# otterley_B_v1_2.net
KiCad netlist of a schematic drawn in EAGLE
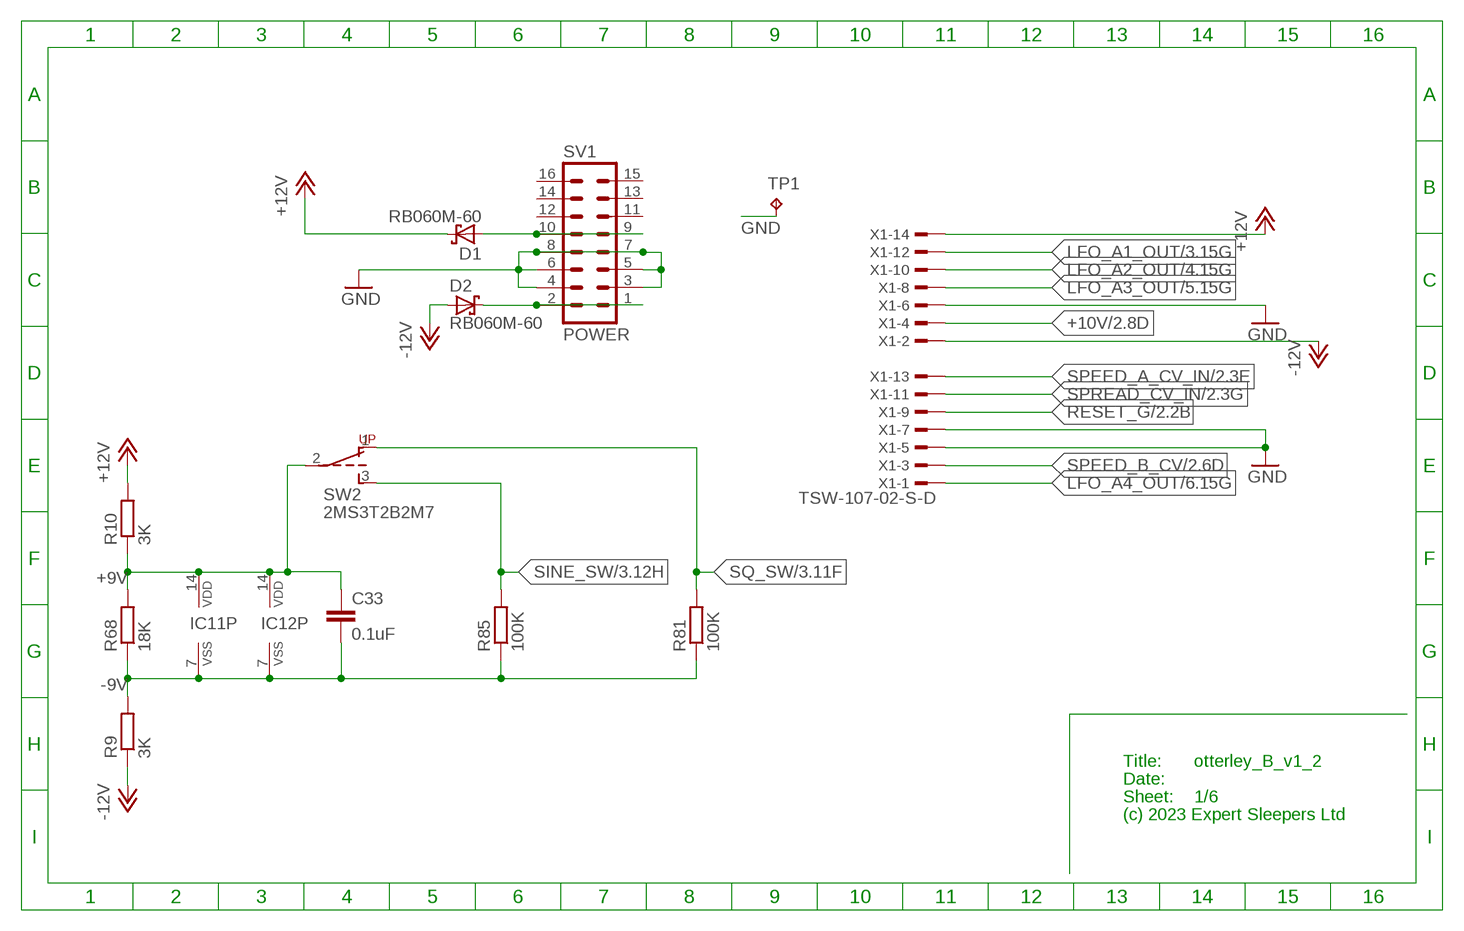
[diagram p0: schematic, sheet 1]
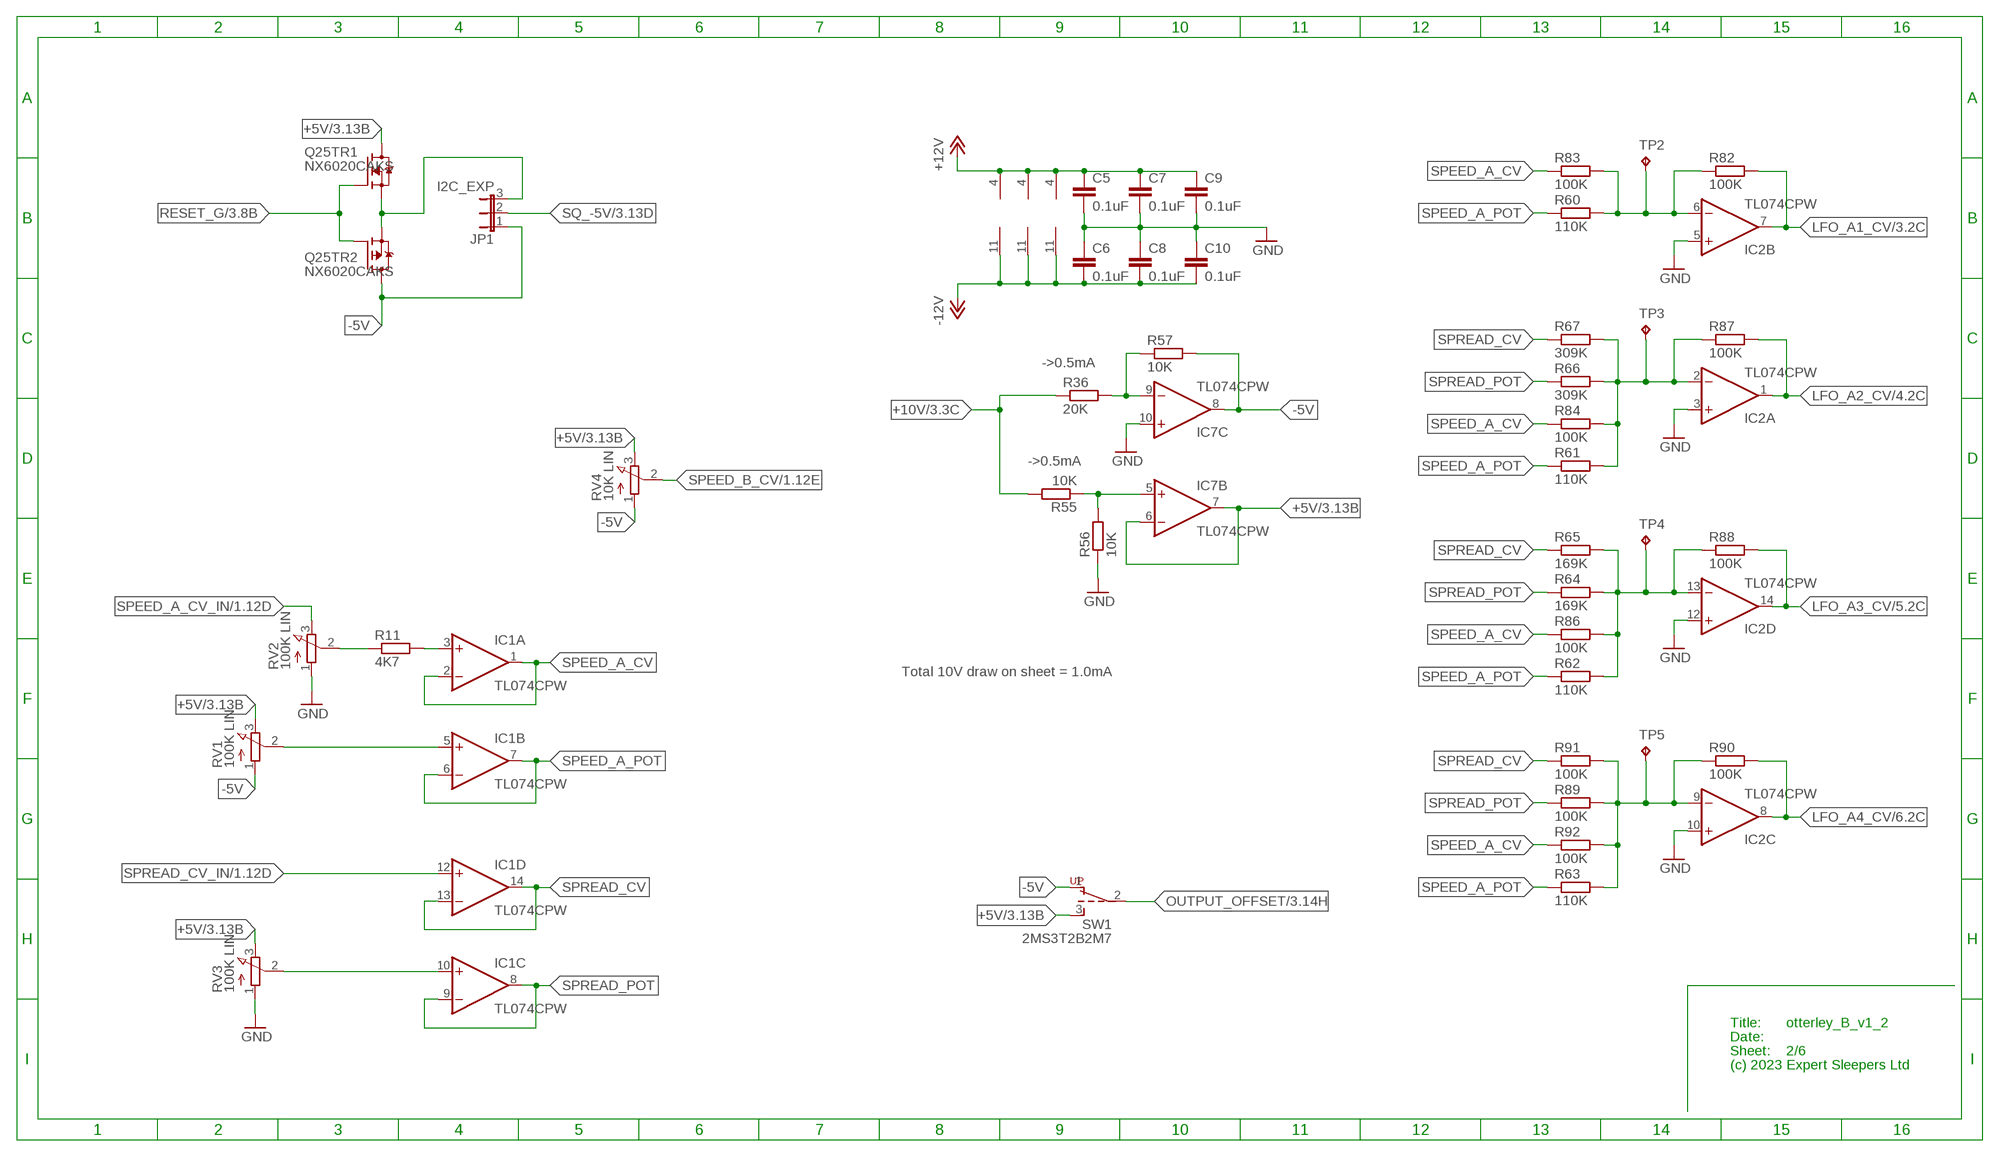
[diagram p1: schematic, sheet 2]
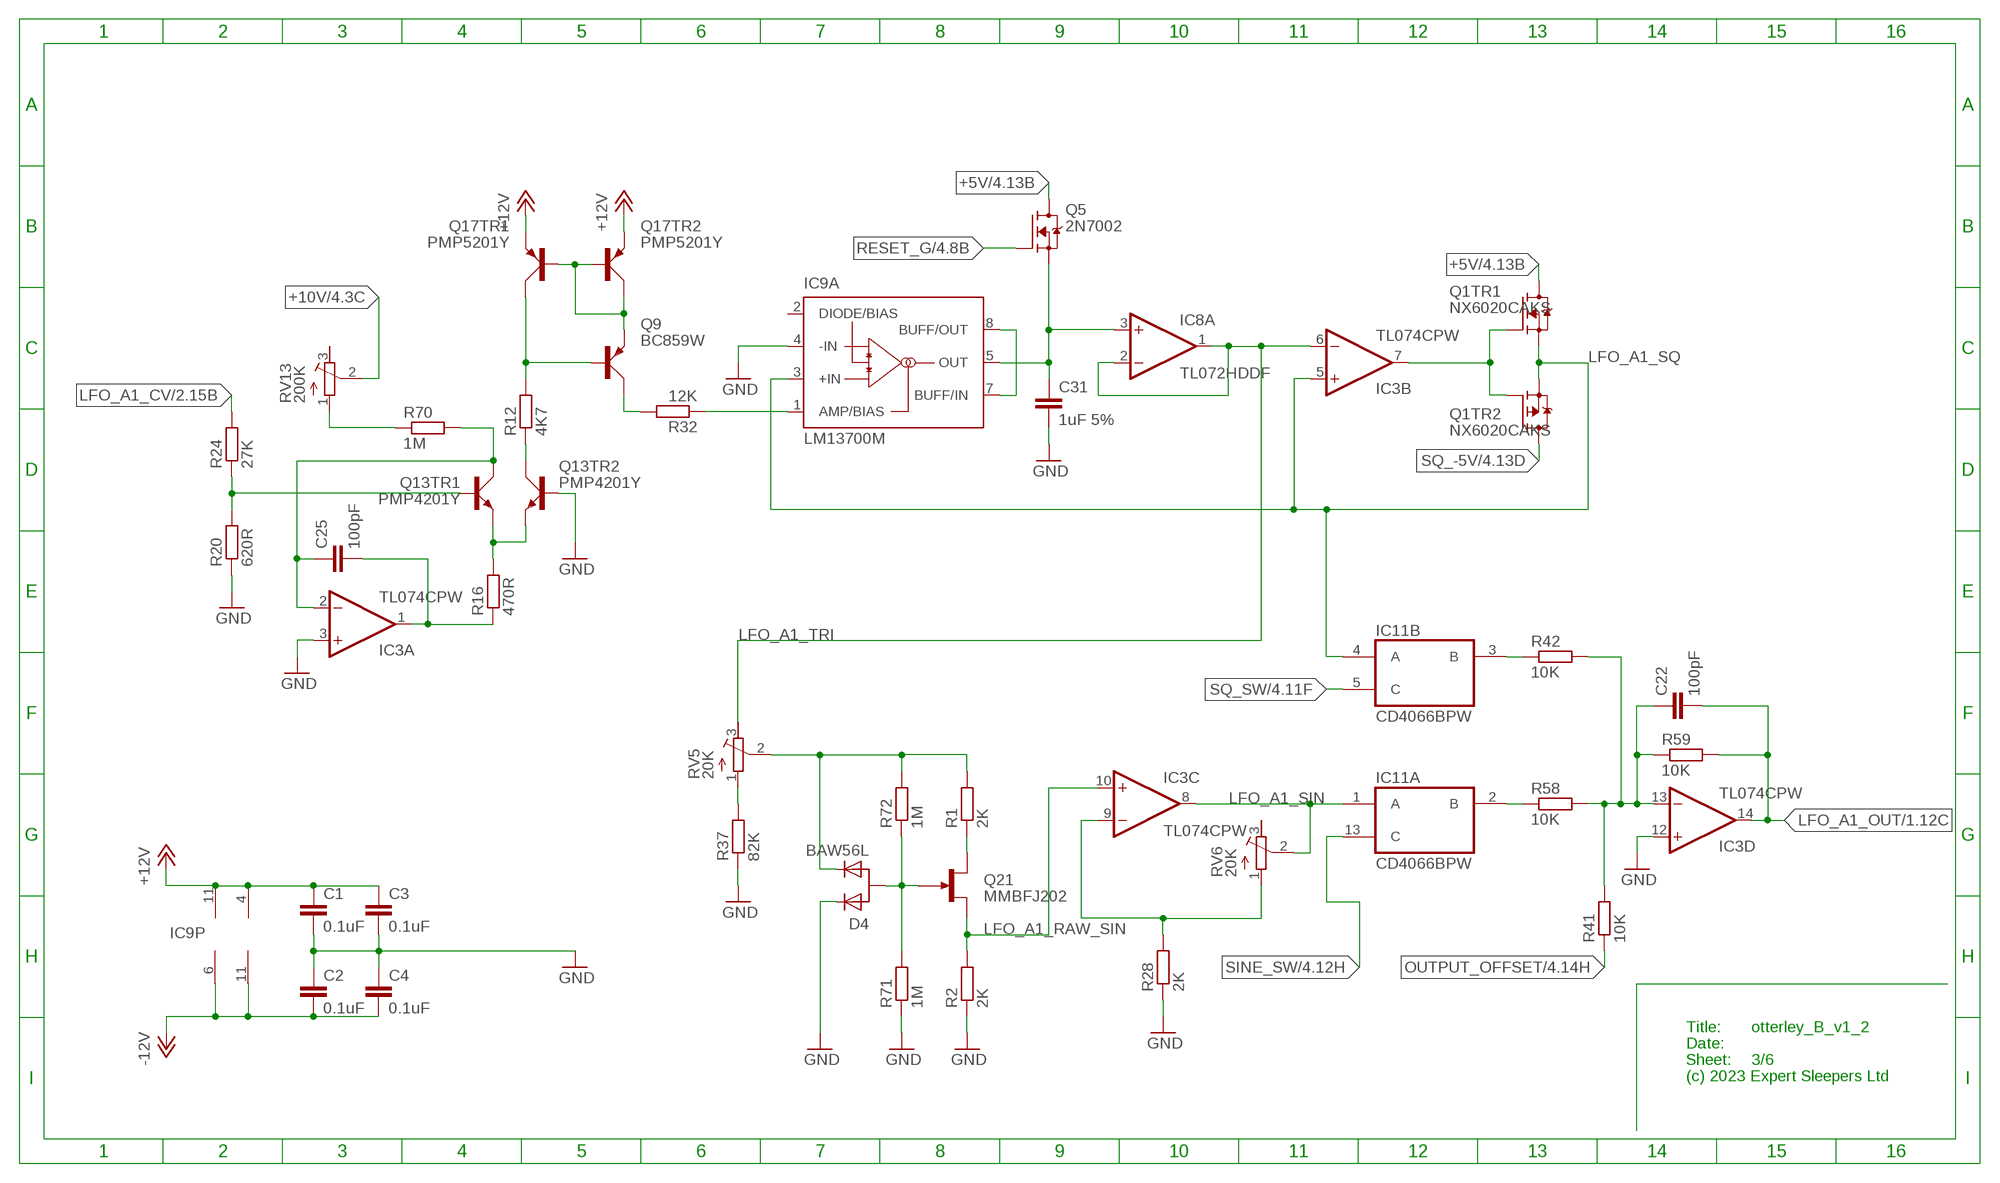
[diagram p2: schematic, sheet 3]
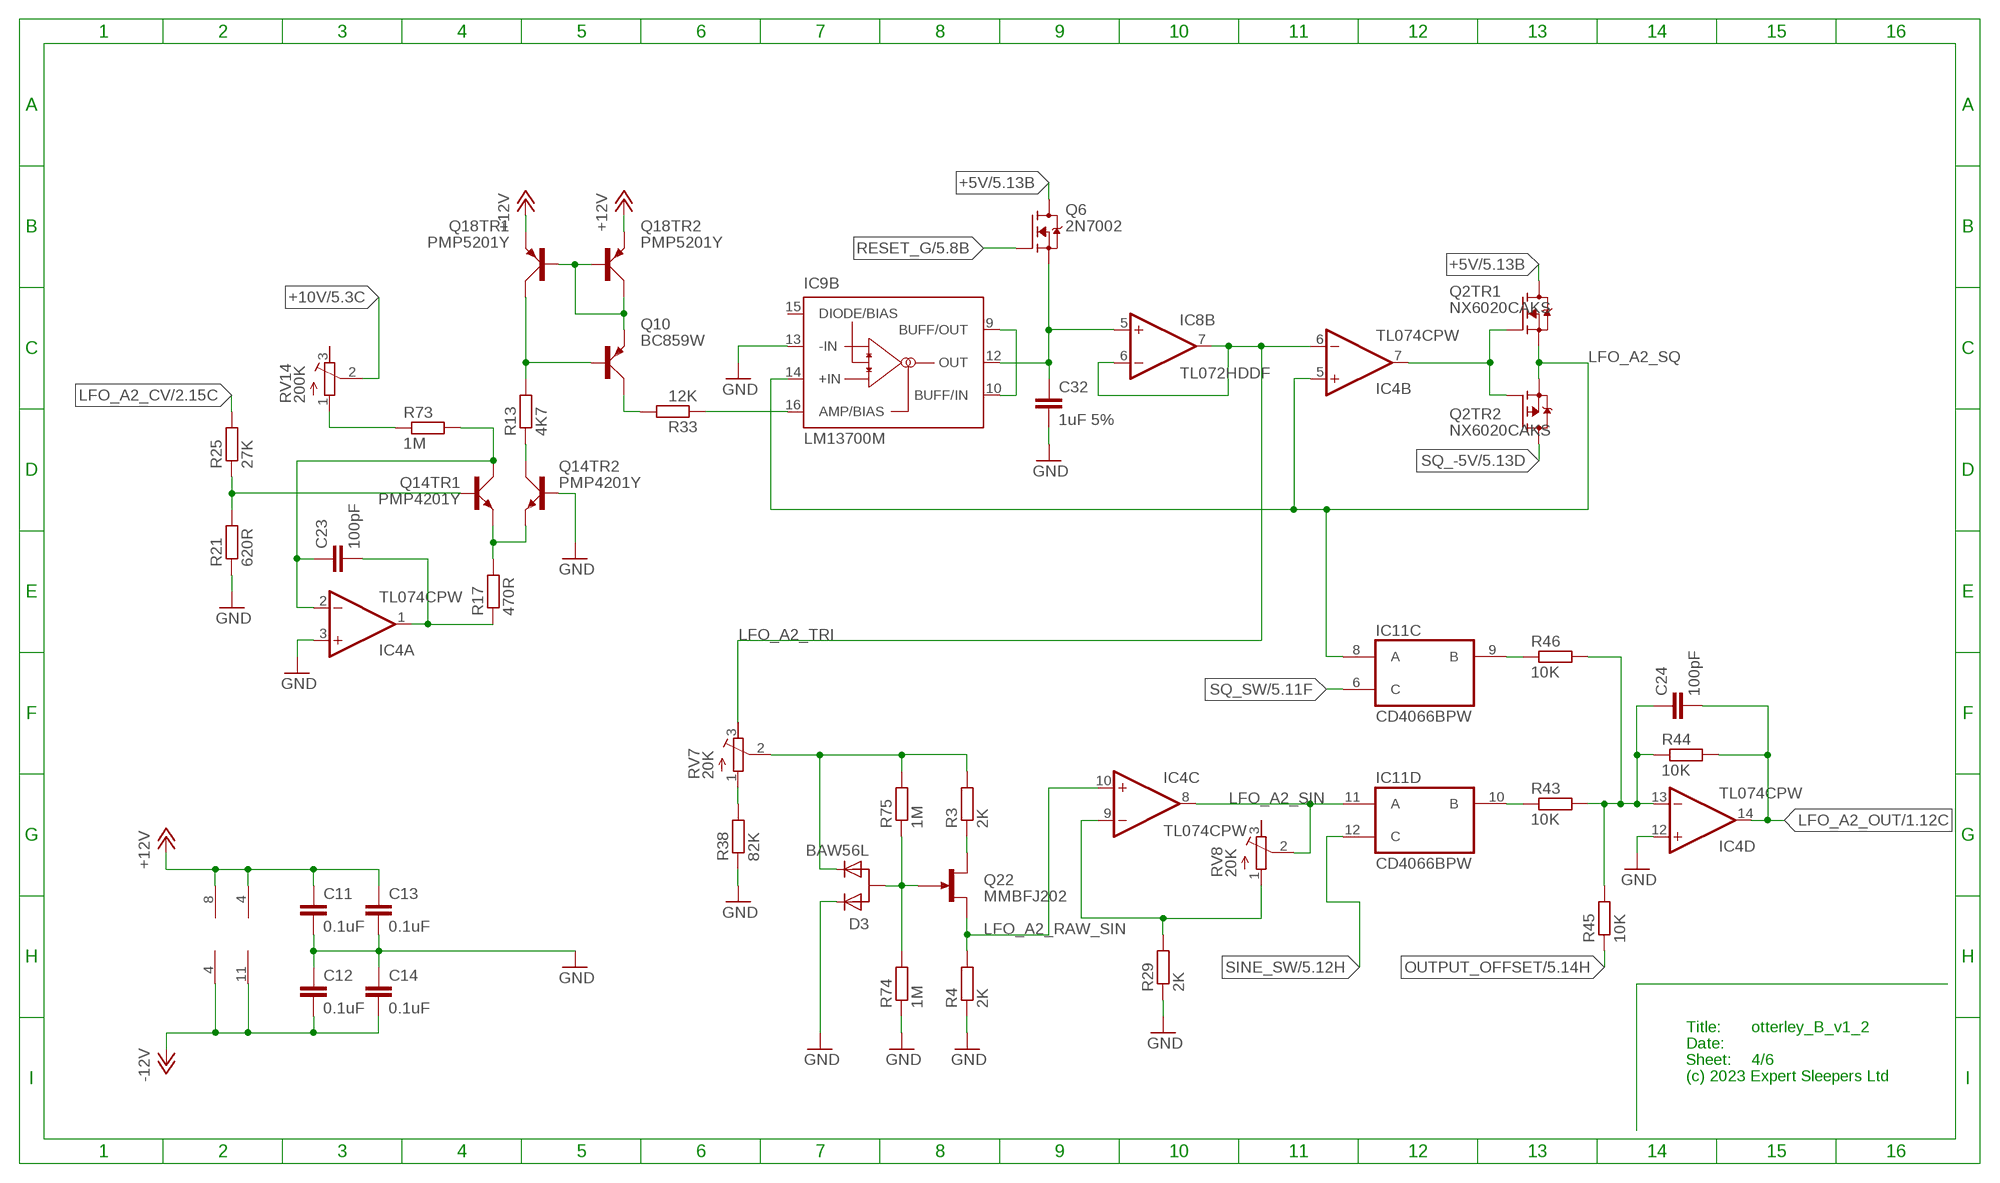
[diagram p3: schematic, sheet 4]
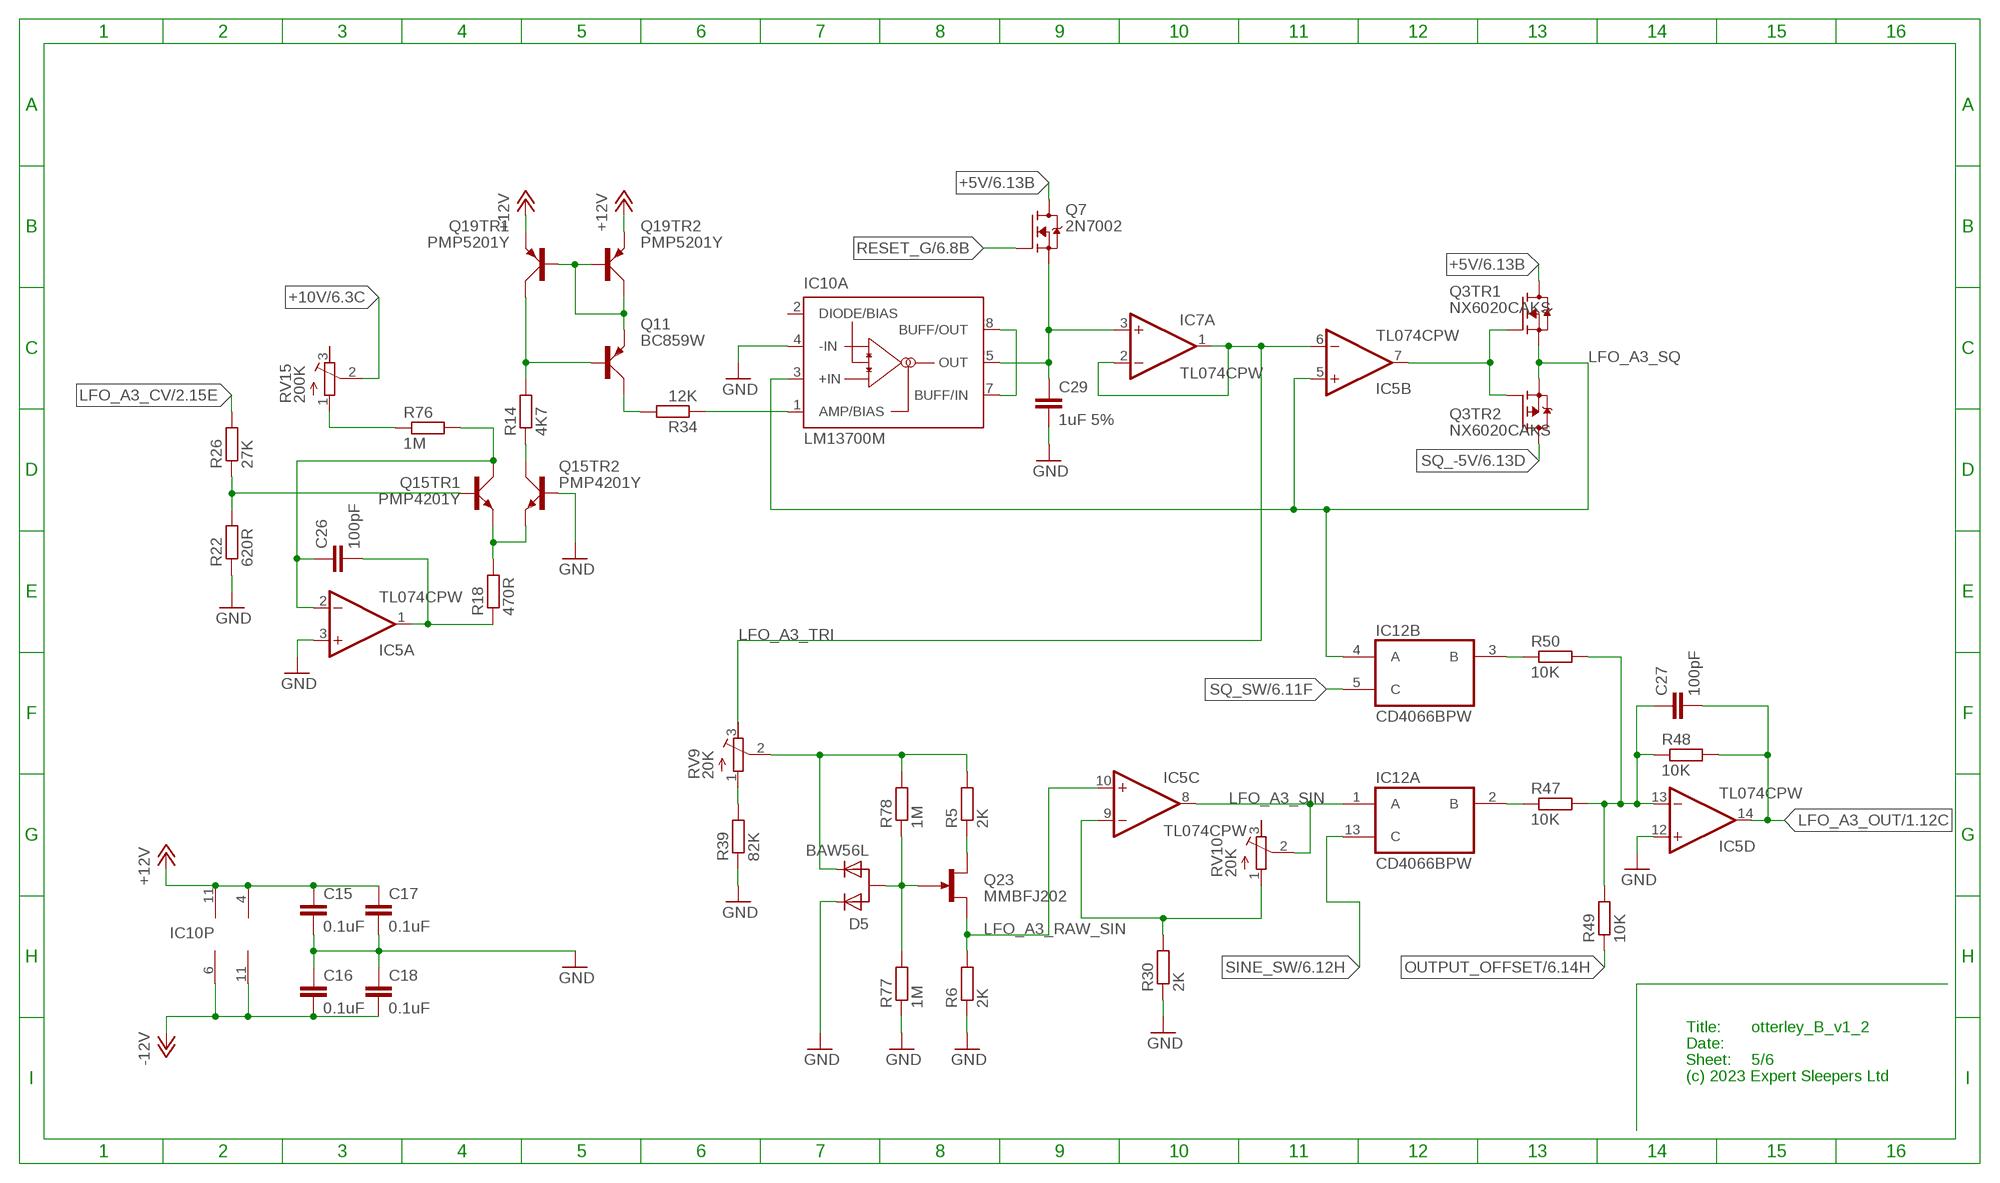
[diagram p4: schematic, sheet 5]
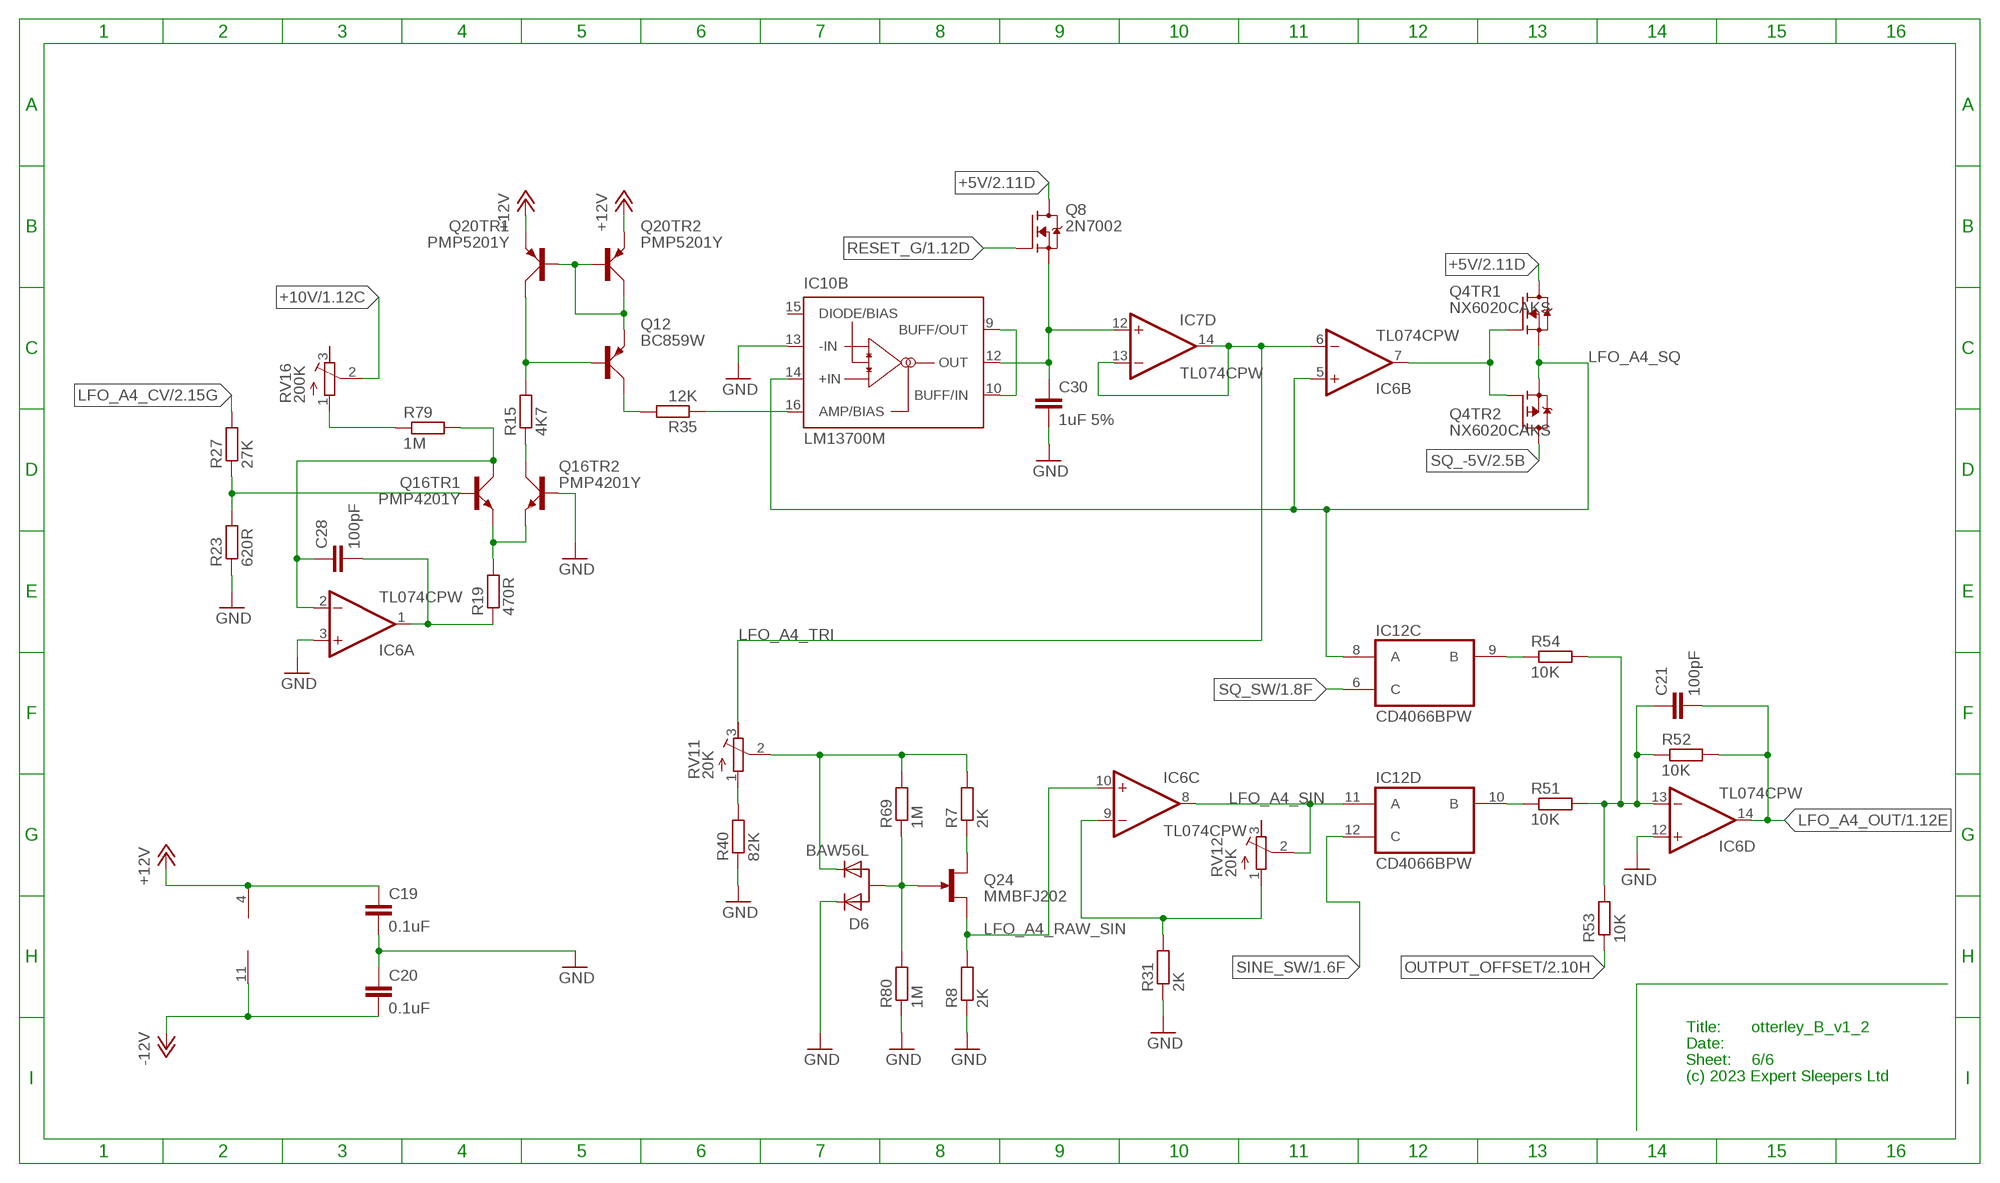
[diagram p5: schematic, sheet 6]

(export (version "E")
  (design (tool "Eeschema 10.0.6"))
  (components
    (comp (ref "C15")
      (value "0.1uF")
      (footprint "eagle-import:C0402")
      (libsource (lib "eagle-import") (part "C-EUC0402"))
    )
    (comp (ref "C16")
      (value "0.1uF")
      (footprint "eagle-import:C0402")
      (libsource (lib "eagle-import") (part "C-EUC0402"))
    )
    (comp (ref "C17")
      (value "0.1uF")
      (footprint "eagle-import:C0402")
      (libsource (lib "eagle-import") (part "C-EUC0402"))
    )
    (comp (ref "C18")
      (value "0.1uF")
      (footprint "eagle-import:C0402")
      (libsource (lib "eagle-import") (part "C-EUC0402"))
    )
    (comp (ref "C26")
      (value "100pF")
      (footprint "eagle-import:C0603")
      (libsource (lib "eagle-import") (part "C-EUC0603"))
    )
    (comp (ref "C27")
      (value "100pF")
      (footprint "eagle-import:C0603")
      (libsource (lib "eagle-import") (part "C-EUC0603"))
    )
    (comp (ref "C29")
      (value "1uF 5%")
      (footprint "eagle-import:C0805")
      (libsource (lib "eagle-import") (part "C-EUC0805"))
    )
    (comp (ref "D5")
      (value "BAW56L")
      (footprint "eagle-import:SOT-23")
      (libsource (lib "eagle-import") (part "BAW56L"))
    )
    (comp (ref "IC5")
      (value "TL074CPW")
      (footprint "eagle-import:PW_R-PDSO-G14")
      (libsource (lib "eagle-import") (part "TL074PW"))
    )
    (comp (ref "IC7")
      (value "TL074CPW")
      (footprint "eagle-import:PW_R-PDSO-G14")
      (libsource (lib "eagle-import") (part "TL074PW"))
    )
    (comp (ref "IC10")
      (value "LM13700M")
      (footprint "eagle-import:SO16")
      (libsource (lib "eagle-import") (part "LM13700M"))
    )
    (comp (ref "IC12")
      (value "CD4066BPW")
      (footprint "eagle-import:PW_R-PDSO-G14")
      (libsource (lib "eagle-import") (part "CD4066BPW"))
    )
    (comp (ref "Q3")
      (value "NX6020CAKS")
      (footprint "eagle-import:SOT363")
      (libsource (lib "eagle-import") (part "NX6020CAKS"))
    )
    (comp (ref "Q7")
      (value "2N7002")
      (footprint "eagle-import:SOT23")
      (libsource (lib "eagle-import") (part "2N7002"))
    )
    (comp (ref "Q11")
      (value "BC859W")
      (footprint "eagle-import:SOT323")
      (libsource (lib "eagle-import") (part "BC859W"))
    )
    (comp (ref "Q15")
      (value "PMP4201Y")
      (footprint "eagle-import:SOT65P210X110-6N")
      (fields
        (field (name "ARROW_PART_NUMBER") "PMP4201Y,135")
        (field (name "MOUSER_PART_NUMBER") "771-PMP4201Y135")
      )
      (libsource (lib "eagle-import") (part "PMP4201Y"))
    )
    (comp (ref "Q19")
      (value "PMP5201Y")
      (footprint "eagle-import:SOT65P210X110-6N")
      (fields
        (field (name "ARROW_PART_NUMBER") "PMP5201Y,135")
        (field (name "MOUSER_PART_NUMBER") "771-PMP5201Y135")
      )
      (libsource (lib "eagle-import") (part "PMP5201Y"))
    )
    (comp (ref "Q23")
      (value "MMBFJ202")
      (footprint "eagle-import:SOT23")
      (libsource (lib "eagle-import") (part "MMBFJ3"))
    )
    (comp (ref "R5")
      (value "2K")
      (footprint "eagle-import:R0603")
      (libsource (lib "eagle-import") (part "R-EU_R0603"))
    )
    (comp (ref "R6")
      (value "2K")
      (footprint "eagle-import:R0603")
      (libsource (lib "eagle-import") (part "R-EU_R0603"))
    )
    (comp (ref "R14")
      (value "4K7")
      (footprint "eagle-import:R0603")
      (libsource (lib "eagle-import") (part "R-EU_R0603"))
    )
    (comp (ref "R18")
      (value "470R")
      (footprint "eagle-import:R0603")
      (libsource (lib "eagle-import") (part "R-EU_R0603"))
    )
    (comp (ref "R22")
      (value "620R")
      (footprint "eagle-import:R0603")
      (libsource (lib "eagle-import") (part "R-EU_R0603"))
    )
    (comp (ref "R26")
      (value "27K")
      (footprint "eagle-import:R0603")
      (libsource (lib "eagle-import") (part "R-EU_R0603"))
    )
    (comp (ref "R30")
      (value "2K")
      (footprint "eagle-import:R0603")
      (libsource (lib "eagle-import") (part "R-EU_R0603"))
    )
    (comp (ref "R34")
      (value "12K")
      (footprint "eagle-import:R0603")
      (libsource (lib "eagle-import") (part "R-EU_R0603"))
    )
    (comp (ref "R39")
      (value "82K")
      (footprint "eagle-import:R0603")
      (libsource (lib "eagle-import") (part "R-EU_R0603"))
    )
    (comp (ref "R47")
      (value "10K")
      (footprint "eagle-import:R0603")
      (libsource (lib "eagle-import") (part "R-EU_R0603"))
    )
    (comp (ref "R48")
      (value "10K")
      (footprint "eagle-import:R0603")
      (libsource (lib "eagle-import") (part "R-EU_R0603"))
    )
    (comp (ref "R49")
      (value "10K")
      (footprint "eagle-import:R0603")
      (libsource (lib "eagle-import") (part "R-EU_R0603"))
    )
    (comp (ref "R50")
      (value "10K")
      (footprint "eagle-import:R0603")
      (libsource (lib "eagle-import") (part "R-EU_R0603"))
    )
    (comp (ref "R76")
      (value "1M")
      (footprint "eagle-import:R0603")
      (libsource (lib "eagle-import") (part "R-EU_R0603"))
    )
    (comp (ref "R77")
      (value "1M")
      (footprint "eagle-import:R0603")
      (libsource (lib "eagle-import") (part "R-EU_R0603"))
    )
    (comp (ref "R78")
      (value "1M")
      (footprint "eagle-import:R0603")
      (libsource (lib "eagle-import") (part "R-EU_R0603"))
    )
    (comp (ref "RV9")
      (value "20K")
      (footprint "eagle-import:TC33X")
      (libsource (lib "eagle-import") (part "TC33X"))
    )
    (comp (ref "RV10")
      (value "20K")
      (footprint "eagle-import:TC33X")
      (libsource (lib "eagle-import") (part "TC33X"))
    )
    (comp (ref "RV15")
      (value "200K")
      (footprint "eagle-import:TC33X")
      (libsource (lib "eagle-import") (part "TC33X"))
    )
    (comp (ref "C1")
      (value "0.1uF")
      (footprint "eagle-import:C0402")
      (libsource (lib "eagle-import") (part "C-EUC0402"))
    )
    (comp (ref "C2")
      (value "0.1uF")
      (footprint "eagle-import:C0402")
      (libsource (lib "eagle-import") (part "C-EUC0402"))
    )
    (comp (ref "C3")
      (value "0.1uF")
      (footprint "eagle-import:C0402")
      (libsource (lib "eagle-import") (part "C-EUC0402"))
    )
    (comp (ref "C4")
      (value "0.1uF")
      (footprint "eagle-import:C0402")
      (libsource (lib "eagle-import") (part "C-EUC0402"))
    )
    (comp (ref "C22")
      (value "100pF")
      (footprint "eagle-import:C0603")
      (libsource (lib "eagle-import") (part "C-EUC0603"))
    )
    (comp (ref "C25")
      (value "100pF")
      (footprint "eagle-import:C0603")
      (libsource (lib "eagle-import") (part "C-EUC0603"))
    )
    (comp (ref "C31")
      (value "1uF 5%")
      (footprint "eagle-import:C0805")
      (libsource (lib "eagle-import") (part "C-EUC0805"))
    )
    (comp (ref "D4")
      (value "BAW56L")
      (footprint "eagle-import:SOT-23")
      (libsource (lib "eagle-import") (part "BAW56L"))
    )
    (comp (ref "IC3")
      (value "TL074CPW")
      (footprint "eagle-import:PW_R-PDSO-G14")
      (libsource (lib "eagle-import") (part "TL074PW"))
    )
    (comp (ref "IC8")
      (value "TL072HDDF")
      (footprint "eagle-import:DDF0008A")
      (libsource (lib "eagle-import") (part "TL072DDFH"))
    )
    (comp (ref "IC9")
      (value "LM13700M")
      (footprint "eagle-import:SO16")
      (libsource (lib "eagle-import") (part "LM13700M"))
    )
    (comp (ref "IC11")
      (value "CD4066BPW")
      (footprint "eagle-import:PW_R-PDSO-G14")
      (libsource (lib "eagle-import") (part "CD4066BPW"))
    )
    (comp (ref "Q1")
      (value "NX6020CAKS")
      (footprint "eagle-import:SOT363")
      (libsource (lib "eagle-import") (part "NX6020CAKS"))
    )
    (comp (ref "Q5")
      (value "2N7002")
      (footprint "eagle-import:SOT23")
      (libsource (lib "eagle-import") (part "2N7002"))
    )
    (comp (ref "Q9")
      (value "BC859W")
      (footprint "eagle-import:SOT323")
      (libsource (lib "eagle-import") (part "BC859W"))
    )
    (comp (ref "Q13")
      (value "PMP4201Y")
      (footprint "eagle-import:SOT65P210X110-6N")
      (fields
        (field (name "ARROW_PART_NUMBER") "PMP4201Y,135")
        (field (name "MOUSER_PART_NUMBER") "771-PMP4201Y135")
      )
      (libsource (lib "eagle-import") (part "PMP4201Y"))
    )
    (comp (ref "Q17")
      (value "PMP5201Y")
      (footprint "eagle-import:SOT65P210X110-6N")
      (fields
        (field (name "ARROW_PART_NUMBER") "PMP5201Y,135")
        (field (name "MOUSER_PART_NUMBER") "771-PMP5201Y135")
      )
      (libsource (lib "eagle-import") (part "PMP5201Y"))
    )
    (comp (ref "Q21")
      (value "MMBFJ202")
      (footprint "eagle-import:SOT23")
      (libsource (lib "eagle-import") (part "MMBFJ3"))
    )
    (comp (ref "R1")
      (value "2K")
      (footprint "eagle-import:R0603")
      (libsource (lib "eagle-import") (part "R-EU_R0603"))
    )
    (comp (ref "R2")
      (value "2K")
      (footprint "eagle-import:R0603")
      (libsource (lib "eagle-import") (part "R-EU_R0603"))
    )
    (comp (ref "R12")
      (value "4K7")
      (footprint "eagle-import:R0603")
      (libsource (lib "eagle-import") (part "R-EU_R0603"))
    )
    (comp (ref "R16")
      (value "470R")
      (footprint "eagle-import:R0603")
      (libsource (lib "eagle-import") (part "R-EU_R0603"))
    )
    (comp (ref "R20")
      (value "620R")
      (footprint "eagle-import:R0603")
      (libsource (lib "eagle-import") (part "R-EU_R0603"))
    )
    (comp (ref "R24")
      (value "27K")
      (footprint "eagle-import:R0603")
      (libsource (lib "eagle-import") (part "R-EU_R0603"))
    )
    (comp (ref "R28")
      (value "2K")
      (footprint "eagle-import:R0603")
      (libsource (lib "eagle-import") (part "R-EU_R0603"))
    )
    (comp (ref "R32")
      (value "12K")
      (footprint "eagle-import:R0603")
      (libsource (lib "eagle-import") (part "R-EU_R0603"))
    )
    (comp (ref "R37")
      (value "82K")
      (footprint "eagle-import:R0603")
      (libsource (lib "eagle-import") (part "R-EU_R0603"))
    )
    (comp (ref "R41")
      (value "10K")
      (footprint "eagle-import:R0603")
      (libsource (lib "eagle-import") (part "R-EU_R0603"))
    )
    (comp (ref "R42")
      (value "10K")
      (footprint "eagle-import:R0603")
      (libsource (lib "eagle-import") (part "R-EU_R0603"))
    )
    (comp (ref "R58")
      (value "10K")
      (footprint "eagle-import:R0603")
      (libsource (lib "eagle-import") (part "R-EU_R0603"))
    )
    (comp (ref "R59")
      (value "10K")
      (footprint "eagle-import:R0603")
      (libsource (lib "eagle-import") (part "R-EU_R0603"))
    )
    (comp (ref "R70")
      (value "1M")
      (footprint "eagle-import:R0603")
      (libsource (lib "eagle-import") (part "R-EU_R0603"))
    )
    (comp (ref "R71")
      (value "1M")
      (footprint "eagle-import:R0603")
      (libsource (lib "eagle-import") (part "R-EU_R0603"))
    )
    (comp (ref "R72")
      (value "1M")
      (footprint "eagle-import:R0603")
      (libsource (lib "eagle-import") (part "R-EU_R0603"))
    )
    (comp (ref "RV5")
      (value "20K")
      (footprint "eagle-import:TC33X")
      (libsource (lib "eagle-import") (part "TC33X"))
    )
    (comp (ref "RV6")
      (value "20K")
      (footprint "eagle-import:TC33X")
      (libsource (lib "eagle-import") (part "TC33X"))
    )
    (comp (ref "RV13")
      (value "200K")
      (footprint "eagle-import:TC33X")
      (libsource (lib "eagle-import") (part "TC33X"))
    )
    (comp (ref "C11")
      (value "0.1uF")
      (footprint "eagle-import:C0402")
      (libsource (lib "eagle-import") (part "C-EUC0402"))
    )
    (comp (ref "C12")
      (value "0.1uF")
      (footprint "eagle-import:C0402")
      (libsource (lib "eagle-import") (part "C-EUC0402"))
    )
    (comp (ref "C13")
      (value "0.1uF")
      (footprint "eagle-import:C0402")
      (libsource (lib "eagle-import") (part "C-EUC0402"))
    )
    (comp (ref "C14")
      (value "0.1uF")
      (footprint "eagle-import:C0402")
      (libsource (lib "eagle-import") (part "C-EUC0402"))
    )
    (comp (ref "C23")
      (value "100pF")
      (footprint "eagle-import:C0603")
      (libsource (lib "eagle-import") (part "C-EUC0603"))
    )
    (comp (ref "C24")
      (value "100pF")
      (footprint "eagle-import:C0603")
      (libsource (lib "eagle-import") (part "C-EUC0603"))
    )
    (comp (ref "C32")
      (value "1uF 5%")
      (footprint "eagle-import:C0805")
      (libsource (lib "eagle-import") (part "C-EUC0805"))
    )
    (comp (ref "D3")
      (value "BAW56L")
      (footprint "eagle-import:SOT-23")
      (libsource (lib "eagle-import") (part "BAW56L"))
    )
    (comp (ref "IC4")
      (value "TL074CPW")
      (footprint "eagle-import:PW_R-PDSO-G14")
      (libsource (lib "eagle-import") (part "TL074PW"))
    )
    (comp (ref "Q2")
      (value "NX6020CAKS")
      (footprint "eagle-import:SOT363")
      (libsource (lib "eagle-import") (part "NX6020CAKS"))
    )
    (comp (ref "Q6")
      (value "2N7002")
      (footprint "eagle-import:SOT23")
      (libsource (lib "eagle-import") (part "2N7002"))
    )
    (comp (ref "Q10")
      (value "BC859W")
      (footprint "eagle-import:SOT323")
      (libsource (lib "eagle-import") (part "BC859W"))
    )
    (comp (ref "Q14")
      (value "PMP4201Y")
      (footprint "eagle-import:SOT65P210X110-6N")
      (fields
        (field (name "ARROW_PART_NUMBER") "PMP4201Y,135")
        (field (name "MOUSER_PART_NUMBER") "771-PMP4201Y135")
      )
      (libsource (lib "eagle-import") (part "PMP4201Y"))
    )
    (comp (ref "Q18")
      (value "PMP5201Y")
      (footprint "eagle-import:SOT65P210X110-6N")
      (fields
        (field (name "ARROW_PART_NUMBER") "PMP5201Y,135")
        (field (name "MOUSER_PART_NUMBER") "771-PMP5201Y135")
      )
      (libsource (lib "eagle-import") (part "PMP5201Y"))
    )
    (comp (ref "Q22")
      (value "MMBFJ202")
      (footprint "eagle-import:SOT23")
      (libsource (lib "eagle-import") (part "MMBFJ3"))
    )
    (comp (ref "R3")
      (value "2K")
      (footprint "eagle-import:R0603")
      (libsource (lib "eagle-import") (part "R-EU_R0603"))
    )
    (comp (ref "R4")
      (value "2K")
      (footprint "eagle-import:R0603")
      (libsource (lib "eagle-import") (part "R-EU_R0603"))
    )
    (comp (ref "R13")
      (value "4K7")
      (footprint "eagle-import:R0603")
      (libsource (lib "eagle-import") (part "R-EU_R0603"))
    )
    (comp (ref "R17")
      (value "470R")
      (footprint "eagle-import:R0603")
      (libsource (lib "eagle-import") (part "R-EU_R0603"))
    )
    (comp (ref "R21")
      (value "620R")
      (footprint "eagle-import:R0603")
      (libsource (lib "eagle-import") (part "R-EU_R0603"))
    )
    (comp (ref "R25")
      (value "27K")
      (footprint "eagle-import:R0603")
      (libsource (lib "eagle-import") (part "R-EU_R0603"))
    )
    (comp (ref "R29")
      (value "2K")
      (footprint "eagle-import:R0603")
      (libsource (lib "eagle-import") (part "R-EU_R0603"))
    )
    (comp (ref "R33")
      (value "12K")
      (footprint "eagle-import:R0603")
      (libsource (lib "eagle-import") (part "R-EU_R0603"))
    )
    (comp (ref "R38")
      (value "82K")
      (footprint "eagle-import:R0603")
      (libsource (lib "eagle-import") (part "R-EU_R0603"))
    )
    (comp (ref "R43")
      (value "10K")
      (footprint "eagle-import:R0603")
      (libsource (lib "eagle-import") (part "R-EU_R0603"))
    )
    (comp (ref "R44")
      (value "10K")
      (footprint "eagle-import:R0603")
      (libsource (lib "eagle-import") (part "R-EU_R0603"))
    )
    (comp (ref "R45")
      (value "10K")
      (footprint "eagle-import:R0603")
      (libsource (lib "eagle-import") (part "R-EU_R0603"))
    )
    (comp (ref "R46")
      (value "10K")
      (footprint "eagle-import:R0603")
      (libsource (lib "eagle-import") (part "R-EU_R0603"))
    )
    (comp (ref "R73")
      (value "1M")
      (footprint "eagle-import:R0603")
      (libsource (lib "eagle-import") (part "R-EU_R0603"))
    )
    (comp (ref "R74")
      (value "1M")
      (footprint "eagle-import:R0603")
      (libsource (lib "eagle-import") (part "R-EU_R0603"))
    )
    (comp (ref "R75")
      (value "1M")
      (footprint "eagle-import:R0603")
      (libsource (lib "eagle-import") (part "R-EU_R0603"))
    )
    (comp (ref "RV7")
      (value "20K")
      (footprint "eagle-import:TC33X")
      (libsource (lib "eagle-import") (part "TC33X"))
    )
    (comp (ref "RV8")
      (value "20K")
      (footprint "eagle-import:TC33X")
      (libsource (lib "eagle-import") (part "TC33X"))
    )
    (comp (ref "RV14")
      (value "200K")
      (footprint "eagle-import:TC33X")
      (libsource (lib "eagle-import") (part "TC33X"))
    )
    (comp (ref "C19")
      (value "0.1uF")
      (footprint "eagle-import:C0402")
      (libsource (lib "eagle-import") (part "C-EUC0402"))
    )
    (comp (ref "C20")
      (value "0.1uF")
      (footprint "eagle-import:C0402")
      (libsource (lib "eagle-import") (part "C-EUC0402"))
    )
    (comp (ref "C21")
      (value "100pF")
      (footprint "eagle-import:C0603")
      (libsource (lib "eagle-import") (part "C-EUC0603"))
    )
    (comp (ref "C28")
      (value "100pF")
      (footprint "eagle-import:C0603")
      (libsource (lib "eagle-import") (part "C-EUC0603"))
    )
    (comp (ref "C30")
      (value "1uF 5%")
      (footprint "eagle-import:C0805")
      (libsource (lib "eagle-import") (part "C-EUC0805"))
    )
    (comp (ref "D6")
      (value "BAW56L")
      (footprint "eagle-import:SOT-23")
      (libsource (lib "eagle-import") (part "BAW56L"))
    )
    (comp (ref "IC6")
      (value "TL074CPW")
      (footprint "eagle-import:PW_R-PDSO-G14")
      (libsource (lib "eagle-import") (part "TL074PW"))
    )
    (comp (ref "Q4")
      (value "NX6020CAKS")
      (footprint "eagle-import:SOT363")
      (libsource (lib "eagle-import") (part "NX6020CAKS"))
    )
    (comp (ref "Q8")
      (value "2N7002")
      (footprint "eagle-import:SOT23")
      (libsource (lib "eagle-import") (part "2N7002"))
    )
    (comp (ref "Q12")
      (value "BC859W")
      (footprint "eagle-import:SOT323")
      (libsource (lib "eagle-import") (part "BC859W"))
    )
    (comp (ref "Q16")
      (value "PMP4201Y")
      (footprint "eagle-import:SOT65P210X110-6N")
      (fields
        (field (name "ARROW_PART_NUMBER") "PMP4201Y,135")
        (field (name "MOUSER_PART_NUMBER") "771-PMP4201Y135")
      )
      (libsource (lib "eagle-import") (part "PMP4201Y"))
    )
    (comp (ref "Q20")
      (value "PMP5201Y")
      (footprint "eagle-import:SOT65P210X110-6N")
      (fields
        (field (name "ARROW_PART_NUMBER") "PMP5201Y,135")
        (field (name "MOUSER_PART_NUMBER") "771-PMP5201Y135")
      )
      (libsource (lib "eagle-import") (part "PMP5201Y"))
    )
    (comp (ref "Q24")
      (value "MMBFJ202")
      (footprint "eagle-import:SOT23")
      (libsource (lib "eagle-import") (part "MMBFJ3"))
    )
    (comp (ref "R7")
      (value "2K")
      (footprint "eagle-import:R0603")
      (libsource (lib "eagle-import") (part "R-EU_R0603"))
    )
    (comp (ref "R8")
      (value "2K")
      (footprint "eagle-import:R0603")
      (libsource (lib "eagle-import") (part "R-EU_R0603"))
    )
    (comp (ref "R15")
      (value "4K7")
      (footprint "eagle-import:R0603")
      (libsource (lib "eagle-import") (part "R-EU_R0603"))
    )
    (comp (ref "R19")
      (value "470R")
      (footprint "eagle-import:R0603")
      (libsource (lib "eagle-import") (part "R-EU_R0603"))
    )
    (comp (ref "R23")
      (value "620R")
      (footprint "eagle-import:R0603")
      (libsource (lib "eagle-import") (part "R-EU_R0603"))
    )
    (comp (ref "R27")
      (value "27K")
      (footprint "eagle-import:R0603")
      (libsource (lib "eagle-import") (part "R-EU_R0603"))
    )
    (comp (ref "R31")
      (value "2K")
      (footprint "eagle-import:R0603")
      (libsource (lib "eagle-import") (part "R-EU_R0603"))
    )
    (comp (ref "R35")
      (value "12K")
      (footprint "eagle-import:R0603")
      (libsource (lib "eagle-import") (part "R-EU_R0603"))
    )
    (comp (ref "R40")
      (value "82K")
      (footprint "eagle-import:R0603")
      (libsource (lib "eagle-import") (part "R-EU_R0603"))
    )
    (comp (ref "R51")
      (value "10K")
      (footprint "eagle-import:R0603")
      (libsource (lib "eagle-import") (part "R-EU_R0603"))
    )
    (comp (ref "R52")
      (value "10K")
      (footprint "eagle-import:R0603")
      (libsource (lib "eagle-import") (part "R-EU_R0603"))
    )
    (comp (ref "R53")
      (value "10K")
      (footprint "eagle-import:R0603")
      (libsource (lib "eagle-import") (part "R-EU_R0603"))
    )
    (comp (ref "R54")
      (value "10K")
      (footprint "eagle-import:R0603")
      (libsource (lib "eagle-import") (part "R-EU_R0603"))
    )
    (comp (ref "R69")
      (value "1M")
      (footprint "eagle-import:R0603")
      (libsource (lib "eagle-import") (part "R-EU_R0603"))
    )
    (comp (ref "R79")
      (value "1M")
      (footprint "eagle-import:R0603")
      (libsource (lib "eagle-import") (part "R-EU_R0603"))
    )
    (comp (ref "R80")
      (value "1M")
      (footprint "eagle-import:R0603")
      (libsource (lib "eagle-import") (part "R-EU_R0603"))
    )
    (comp (ref "RV11")
      (value "20K")
      (footprint "eagle-import:TC33X")
      (libsource (lib "eagle-import") (part "TC33X"))
    )
    (comp (ref "RV12")
      (value "20K")
      (footprint "eagle-import:TC33X")
      (libsource (lib "eagle-import") (part "TC33X"))
    )
    (comp (ref "RV16")
      (value "200K")
      (footprint "eagle-import:TC33X")
      (libsource (lib "eagle-import") (part "TC33X"))
    )
    (comp (ref "C33")
      (value "0.1uF")
      (footprint "eagle-import:C0402")
      (libsource (lib "eagle-import") (part "C-EUC0402"))
    )
    (comp (ref "D1")
      (value "RB060M-60")
      (footprint "eagle-import:SOD123FL")
      (libsource (lib "eagle-import") (part "RB060M-60"))
    )
    (comp (ref "D2")
      (value "RB060M-60")
      (footprint "eagle-import:SOD123FL")
      (libsource (lib "eagle-import") (part "RB060M-60"))
    )
    (comp (ref "R9")
      (value "3K")
      (footprint "eagle-import:R0603")
      (libsource (lib "eagle-import") (part "R-EU_R0603"))
    )
    (comp (ref "R10")
      (value "3K")
      (footprint "eagle-import:R0603")
      (libsource (lib "eagle-import") (part "R-EU_R0603"))
    )
    (comp (ref "R68")
      (value "18K")
      (footprint "eagle-import:R0603")
      (libsource (lib "eagle-import") (part "R-EU_R0603"))
    )
    (comp (ref "R81")
      (value "100K")
      (footprint "eagle-import:R0603")
      (libsource (lib "eagle-import") (part "R-EU_R0603"))
    )
    (comp (ref "R85")
      (value "100K")
      (footprint "eagle-import:R0603")
      (libsource (lib "eagle-import") (part "R-EU_R0603"))
    )
    (comp (ref "SV1")
      (value "POWER")
      (footprint "eagle-import:ML16")
      (libsource (lib "eagle-import") (part "ML16"))
    )
    (comp (ref "SW2")
      (value "2MS3T2B2M7")
      (footprint "eagle-import:2MS1T2B2M7RE")
      (libsource (lib "eagle-import") (part "2MS3M7T2B2"))
    )
    (comp (ref "TP1")
      (value "RA2")
      (footprint "eagle-import:P1-13")
      (libsource (lib "eagle-import") (part "TPPAD1-13"))
    )
    (comp (ref "X1")
      (value "TSW-107-02-S-D")
      (footprint "eagle-import:TSW-107-02-S-D")
      (libsource (lib "eagle-import") (part "TSW-107-02-S-D"))
    )
    (comp (ref "C5")
      (value "0.1uF")
      (footprint "eagle-import:C0402")
      (libsource (lib "eagle-import") (part "C-EUC0402"))
    )
    (comp (ref "C6")
      (value "0.1uF")
      (footprint "eagle-import:C0402")
      (libsource (lib "eagle-import") (part "C-EUC0402"))
    )
    (comp (ref "C7")
      (value "0.1uF")
      (footprint "eagle-import:C0402")
      (libsource (lib "eagle-import") (part "C-EUC0402"))
    )
    (comp (ref "C8")
      (value "0.1uF")
      (footprint "eagle-import:C0402")
      (libsource (lib "eagle-import") (part "C-EUC0402"))
    )
    (comp (ref "C9")
      (value "0.1uF")
      (footprint "eagle-import:C0402")
      (libsource (lib "eagle-import") (part "C-EUC0402"))
    )
    (comp (ref "C10")
      (value "0.1uF")
      (footprint "eagle-import:C0402")
      (libsource (lib "eagle-import") (part "C-EUC0402"))
    )
    (comp (ref "IC1")
      (value "TL074CPW")
      (footprint "eagle-import:PW_R-PDSO-G14")
      (libsource (lib "eagle-import") (part "TL074PW"))
    )
    (comp (ref "IC2")
      (value "TL074CPW")
      (footprint "eagle-import:PW_R-PDSO-G14")
      (libsource (lib "eagle-import") (part "TL074PW"))
    )
    (comp (ref "JP1")
      (value "I2C_EXP")
      (footprint "eagle-import:JP2")
      (libsource (lib "eagle-import") (part "JP2E"))
    )
    (comp (ref "Q25")
      (value "NX6020CAKS")
      (footprint "eagle-import:SOT363")
      (libsource (lib "eagle-import") (part "NX6020CAKS"))
    )
    (comp (ref "R11")
      (value "4K7")
      (footprint "eagle-import:R0603")
      (libsource (lib "eagle-import") (part "R-EU_R0603"))
    )
    (comp (ref "R36")
      (value "20K")
      (footprint "eagle-import:R0603")
      (libsource (lib "eagle-import") (part "R-EU_R0603"))
    )
    (comp (ref "R55")
      (value "10K")
      (footprint "eagle-import:R0603")
      (libsource (lib "eagle-import") (part "R-EU_R0603"))
    )
    (comp (ref "R56")
      (value "10K")
      (footprint "eagle-import:R0603")
      (libsource (lib "eagle-import") (part "R-EU_R0603"))
    )
    (comp (ref "R57")
      (value "10K")
      (footprint "eagle-import:R0603")
      (libsource (lib "eagle-import") (part "R-EU_R0603"))
    )
    (comp (ref "R60")
      (value "110K")
      (footprint "eagle-import:R0603")
      (libsource (lib "eagle-import") (part "R-EU_R0603"))
    )
    (comp (ref "R61")
      (value "110K")
      (footprint "eagle-import:R0603")
      (libsource (lib "eagle-import") (part "R-EU_R0603"))
    )
    (comp (ref "R62")
      (value "110K")
      (footprint "eagle-import:R0603")
      (libsource (lib "eagle-import") (part "R-EU_R0603"))
    )
    (comp (ref "R63")
      (value "110K")
      (footprint "eagle-import:R0603")
      (libsource (lib "eagle-import") (part "R-EU_R0603"))
    )
    (comp (ref "R64")
      (value "169K")
      (footprint "eagle-import:R0603")
      (libsource (lib "eagle-import") (part "R-EU_R0603"))
    )
    (comp (ref "R65")
      (value "169K")
      (footprint "eagle-import:R0603")
      (libsource (lib "eagle-import") (part "R-EU_R0603"))
    )
    (comp (ref "R66")
      (value "309K")
      (footprint "eagle-import:R0603")
      (libsource (lib "eagle-import") (part "R-EU_R0603"))
    )
    (comp (ref "R67")
      (value "309K")
      (footprint "eagle-import:R0603")
      (libsource (lib "eagle-import") (part "R-EU_R0603"))
    )
    (comp (ref "R82")
      (value "100K")
      (footprint "eagle-import:R0603")
      (libsource (lib "eagle-import") (part "R-EU_R0603"))
    )
    (comp (ref "R83")
      (value "100K")
      (footprint "eagle-import:R0603")
      (libsource (lib "eagle-import") (part "R-EU_R0603"))
    )
    (comp (ref "R84")
      (value "100K")
      (footprint "eagle-import:R0603")
      (libsource (lib "eagle-import") (part "R-EU_R0603"))
    )
    (comp (ref "R86")
      (value "100K")
      (footprint "eagle-import:R0603")
      (libsource (lib "eagle-import") (part "R-EU_R0603"))
    )
    (comp (ref "R87")
      (value "100K")
      (footprint "eagle-import:R0603")
      (libsource (lib "eagle-import") (part "R-EU_R0603"))
    )
    (comp (ref "R88")
      (value "100K")
      (footprint "eagle-import:R0603")
      (libsource (lib "eagle-import") (part "R-EU_R0603"))
    )
    (comp (ref "R89")
      (value "100K")
      (footprint "eagle-import:R0603")
      (libsource (lib "eagle-import") (part "R-EU_R0603"))
    )
    (comp (ref "R90")
      (value "100K")
      (footprint "eagle-import:R0603")
      (libsource (lib "eagle-import") (part "R-EU_R0603"))
    )
    (comp (ref "R91")
      (value "100K")
      (footprint "eagle-import:R0603")
      (libsource (lib "eagle-import") (part "R-EU_R0603"))
    )
    (comp (ref "R92")
      (value "100K")
      (footprint "eagle-import:R0603")
      (libsource (lib "eagle-import") (part "R-EU_R0603"))
    )
    (comp (ref "RV1")
      (value "100K LIN")
      (footprint "eagle-import:RD1610NOA0X")
      (libsource (lib "eagle-import") (part "RD1610NOA0X"))
    )
    (comp (ref "RV2")
      (value "100K LIN")
      (footprint "eagle-import:RD1610NOA0X")
      (libsource (lib "eagle-import") (part "RD1610NOA0X"))
    )
    (comp (ref "RV3")
      (value "100K LIN")
      (footprint "eagle-import:RD1610NOA0X")
      (libsource (lib "eagle-import") (part "RD1610NOA0X"))
    )
    (comp (ref "RV4")
      (value "10K LIN")
      (footprint "eagle-import:RD1610NOA0X")
      (libsource (lib "eagle-import") (part "RD1610NOA0X"))
    )
    (comp (ref "SW1")
      (value "2MS3T2B2M7")
      (footprint "eagle-import:2MS1T2B2M7RE")
      (libsource (lib "eagle-import") (part "2MS3M7T2B2"))
    )
    (comp (ref "TP2")
      (value "RA2")
      (footprint "eagle-import:P1-13")
      (libsource (lib "eagle-import") (part "TPPAD1-13"))
    )
    (comp (ref "TP3")
      (value "RA2")
      (footprint "eagle-import:P1-13")
      (libsource (lib "eagle-import") (part "TPPAD1-13"))
    )
    (comp (ref "TP4")
      (value "RA2")
      (footprint "eagle-import:P1-13")
      (libsource (lib "eagle-import") (part "TPPAD1-13"))
    )
    (comp (ref "TP5")
      (value "RA2")
      (footprint "eagle-import:P1-13")
      (libsource (lib "eagle-import") (part "TPPAD1-13"))
    )
  )
  (nets
    (net (code "1") (name "+5V") (class "Default")
      (node (ref "IC7") (pin "6") (pinfunction "-IN_6") (pintype "input"))
      (node (ref "IC7") (pin "7") (pinfunction "OUT_7") (pintype "output"))
      (node (ref "Q1") (pin "6") (pinfunction "D_6") (pintype "passive"))
      (node (ref "Q2") (pin "6") (pinfunction "D_6") (pintype "passive"))
      (node (ref "Q25") (pin "6") (pinfunction "D_6") (pintype "passive"))
      (node (ref "Q3") (pin "6") (pinfunction "D_6") (pintype "passive"))
      (node (ref "Q4") (pin "6") (pinfunction "D_6") (pintype "passive"))
      (node (ref "Q5") (pin "3") (pinfunction "D_3") (pintype "passive"))
      (node (ref "Q6") (pin "3") (pinfunction "D_3") (pintype "passive"))
      (node (ref "Q7") (pin "3") (pinfunction "D_3") (pintype "passive"))
      (node (ref "Q8") (pin "3") (pinfunction "D_3") (pintype "passive"))
      (node (ref "RV1") (pin "3") (pinfunction "E_3") (pintype "passive"))
      (node (ref "RV3") (pin "3") (pinfunction "E_3") (pintype "passive"))
      (node (ref "RV4") (pin "3") (pinfunction "E_3") (pintype "passive"))
      (node (ref "SW1") (pin "3") (pinfunction "RD_3") (pintype "passive"))
    )
    (net (code "2") (name "+9V") (class "Default")
      (node (ref "C33") (pin "1") (pinfunction "1_1") (pintype "passive"))
      (node (ref "IC11") (pin "14") (pinfunction "VDD_14") (pintype "power_in"))
      (node (ref "IC12") (pin "14") (pinfunction "VDD_14") (pintype "power_in"))
      (node (ref "R10") (pin "1") (pinfunction "1_1") (pintype "passive"))
      (node (ref "R68") (pin "2") (pinfunction "2_2") (pintype "passive"))
      (node (ref "SW2") (pin "2") (pinfunction "PR_2") (pintype "passive"))
    )
    (net (code "3") (name "+10V") (class "Default")
      (node (ref "R36") (pin "1") (pinfunction "1_1") (pintype "passive"))
      (node (ref "R55") (pin "2") (pinfunction "2_2") (pintype "passive"))
      (node (ref "RV13") (pin "2") (pinfunction "S_2") (pintype "passive"))
      (node (ref "RV14") (pin "2") (pinfunction "S_2") (pintype "passive"))
      (node (ref "RV15") (pin "2") (pinfunction "S_2") (pintype "passive"))
      (node (ref "RV16") (pin "2") (pinfunction "S_2") (pintype "passive"))
      (node (ref "X1") (pin "4") (pinfunction "1_4") (pintype "passive"))
    )
    (net (code "4") (name "+12V") (class "Default")
      (node (ref "C1") (pin "1") (pinfunction "1_1") (pintype "passive"))
      (node (ref "C11") (pin "1") (pinfunction "1_1") (pintype "passive"))
      (node (ref "C13") (pin "1") (pinfunction "1_1") (pintype "passive"))
      (node (ref "C15") (pin "1") (pinfunction "1_1") (pintype "passive"))
      (node (ref "C17") (pin "1") (pinfunction "1_1") (pintype "passive"))
      (node (ref "C19") (pin "1") (pinfunction "1_1") (pintype "passive"))
      (node (ref "C3") (pin "1") (pinfunction "1_1") (pintype "passive"))
      (node (ref "C5") (pin "1") (pinfunction "1_1") (pintype "passive"))
      (node (ref "C7") (pin "1") (pinfunction "1_1") (pintype "passive"))
      (node (ref "C9") (pin "1") (pinfunction "1_1") (pintype "passive"))
      (node (ref "D1") (pin "C") (pinfunction "C_C") (pintype "passive"))
      (node (ref "IC1") (pin "4") (pinfunction "V+_4") (pintype "power_in"))
      (node (ref "IC10") (pin "11") (pinfunction "V+_11") (pintype "power_in"))
      (node (ref "IC2") (pin "4") (pinfunction "V+_4") (pintype "power_in"))
      (node (ref "IC3") (pin "4") (pinfunction "V+_4") (pintype "power_in"))
      (node (ref "IC4") (pin "4") (pinfunction "V+_4") (pintype "power_in"))
      (node (ref "IC5") (pin "4") (pinfunction "V+_4") (pintype "power_in"))
      (node (ref "IC6") (pin "4") (pinfunction "V+_4") (pintype "power_in"))
      (node (ref "IC7") (pin "4") (pinfunction "V+_4") (pintype "power_in"))
      (node (ref "IC8") (pin "8") (pinfunction "V+_8") (pintype "power_in"))
      (node (ref "IC9") (pin "11") (pinfunction "V+_11") (pintype "power_in"))
      (node (ref "Q17") (pin "4") (pinfunction "E_4") (pintype "passive"))
      (node (ref "Q17") (pin "5") (pinfunction "E_5") (pintype "passive"))
      (node (ref "Q18") (pin "4") (pinfunction "E_4") (pintype "passive"))
      (node (ref "Q18") (pin "5") (pinfunction "E_5") (pintype "passive"))
      (node (ref "Q19") (pin "4") (pinfunction "E_4") (pintype "passive"))
      (node (ref "Q19") (pin "5") (pinfunction "E_5") (pintype "passive"))
      (node (ref "Q20") (pin "4") (pinfunction "E_4") (pintype "passive"))
      (node (ref "Q20") (pin "5") (pinfunction "E_5") (pintype "passive"))
      (node (ref "R10") (pin "2") (pinfunction "2_2") (pintype "passive"))
      (node (ref "X1") (pin "14") (pinfunction "1_14") (pintype "passive"))
    )
    (net (code "5") (name "-5V") (class "Default")
      (node (ref "IC7") (pin "8") (pinfunction "OUT_8") (pintype "output"))
      (node (ref "JP1") (pin "1") (pinfunction "1_1") (pintype "passive"))
      (node (ref "Q25") (pin "3") (pinfunction "D_3") (pintype "passive"))
      (node (ref "R57") (pin "2") (pinfunction "2_2") (pintype "passive"))
      (node (ref "RV1") (pin "1") (pinfunction "A_1") (pintype "passive"))
      (node (ref "RV4") (pin "1") (pinfunction "A_1") (pintype "passive"))
      (node (ref "SW1") (pin "1") (pinfunction "RU_1") (pintype "passive"))
    )
    (net (code "6") (name "-9V") (class "Default")
      (node (ref "C33") (pin "2") (pinfunction "2_2") (pintype "passive"))
      (node (ref "IC11") (pin "7") (pinfunction "VSS_7") (pintype "power_in"))
      (node (ref "IC12") (pin "7") (pinfunction "VSS_7") (pintype "power_in"))
      (node (ref "R68") (pin "1") (pinfunction "1_1") (pintype "passive"))
      (node (ref "R81") (pin "1") (pinfunction "1_1") (pintype "passive"))
      (node (ref "R85") (pin "1") (pinfunction "1_1") (pintype "passive"))
      (node (ref "R9") (pin "2") (pinfunction "2_2") (pintype "passive"))
    )
    (net (code "7") (name "-12V") (class "Default")
      (node (ref "C10") (pin "2") (pinfunction "2_2") (pintype "passive"))
      (node (ref "C12") (pin "2") (pinfunction "2_2") (pintype "passive"))
      (node (ref "C14") (pin "2") (pinfunction "2_2") (pintype "passive"))
      (node (ref "C16") (pin "2") (pinfunction "2_2") (pintype "passive"))
      (node (ref "C18") (pin "2") (pinfunction "2_2") (pintype "passive"))
      (node (ref "C2") (pin "2") (pinfunction "2_2") (pintype "passive"))
      (node (ref "C20") (pin "2") (pinfunction "2_2") (pintype "passive"))
      (node (ref "C4") (pin "2") (pinfunction "2_2") (pintype "passive"))
      (node (ref "C6") (pin "2") (pinfunction "2_2") (pintype "passive"))
      (node (ref "C8") (pin "2") (pinfunction "2_2") (pintype "passive"))
      (node (ref "D2") (pin "A") (pinfunction "A_A") (pintype "passive"))
      (node (ref "IC1") (pin "11") (pinfunction "V-_11") (pintype "power_in"))
      (node (ref "IC10") (pin "6") (pinfunction "V-_6") (pintype "power_in"))
      (node (ref "IC2") (pin "11") (pinfunction "V-_11") (pintype "power_in"))
      (node (ref "IC3") (pin "11") (pinfunction "V-_11") (pintype "power_in"))
      (node (ref "IC4") (pin "11") (pinfunction "V-_11") (pintype "power_in"))
      (node (ref "IC5") (pin "11") (pinfunction "V-_11") (pintype "power_in"))
      (node (ref "IC6") (pin "11") (pinfunction "V-_11") (pintype "power_in"))
      (node (ref "IC7") (pin "11") (pinfunction "V-_11") (pintype "power_in"))
      (node (ref "IC8") (pin "4") (pinfunction "V-_4") (pintype "power_in"))
      (node (ref "IC9") (pin "6") (pinfunction "V-_6") (pintype "power_in"))
      (node (ref "R9") (pin "1") (pinfunction "1_1") (pintype "passive"))
      (node (ref "X1") (pin "2") (pinfunction "1_2") (pintype "passive"))
    )
    (net (code "8") (name "GND") (class "Default")
      (node (ref "C1") (pin "2") (pinfunction "2_2") (pintype "passive"))
      (node (ref "C10") (pin "1") (pinfunction "1_1") (pintype "passive"))
      (node (ref "C11") (pin "2") (pinfunction "2_2") (pintype "passive"))
      (node (ref "C12") (pin "1") (pinfunction "1_1") (pintype "passive"))
      (node (ref "C13") (pin "2") (pinfunction "2_2") (pintype "passive"))
      (node (ref "C14") (pin "1") (pinfunction "1_1") (pintype "passive"))
      (node (ref "C15") (pin "2") (pinfunction "2_2") (pintype "passive"))
      (node (ref "C16") (pin "1") (pinfunction "1_1") (pintype "passive"))
      (node (ref "C17") (pin "2") (pinfunction "2_2") (pintype "passive"))
      (node (ref "C18") (pin "1") (pinfunction "1_1") (pintype "passive"))
      (node (ref "C19") (pin "2") (pinfunction "2_2") (pintype "passive"))
      (node (ref "C2") (pin "1") (pinfunction "1_1") (pintype "passive"))
      (node (ref "C20") (pin "1") (pinfunction "1_1") (pintype "passive"))
      (node (ref "C29") (pin "2") (pinfunction "2_2") (pintype "passive"))
      (node (ref "C3") (pin "2") (pinfunction "2_2") (pintype "passive"))
      (node (ref "C30") (pin "2") (pinfunction "2_2") (pintype "passive"))
      (node (ref "C31") (pin "2") (pinfunction "2_2") (pintype "passive"))
      (node (ref "C32") (pin "2") (pinfunction "2_2") (pintype "passive"))
      (node (ref "C4") (pin "1") (pinfunction "1_1") (pintype "passive"))
      (node (ref "C5") (pin "2") (pinfunction "2_2") (pintype "passive"))
      (node (ref "C6") (pin "1") (pinfunction "1_1") (pintype "passive"))
      (node (ref "C7") (pin "2") (pinfunction "2_2") (pintype "passive"))
      (node (ref "C8") (pin "1") (pinfunction "1_1") (pintype "passive"))
      (node (ref "C9") (pin "2") (pinfunction "2_2") (pintype "passive"))
      (node (ref "D3") (pin "1") (pinfunction "C1_1") (pintype "passive"))
      (node (ref "D4") (pin "1") (pinfunction "C1_1") (pintype "passive"))
      (node (ref "D5") (pin "1") (pinfunction "C1_1") (pintype "passive"))
      (node (ref "D6") (pin "1") (pinfunction "C1_1") (pintype "passive"))
      (node (ref "IC10") (pin "13") (pinfunction "-IN_13") (pintype "input"))
      (node (ref "IC10") (pin "4") (pinfunction "-IN_4") (pintype "input"))
      (node (ref "IC2") (pin "10") (pinfunction "+IN_10") (pintype "input"))
      (node (ref "IC2") (pin "12") (pinfunction "+IN_12") (pintype "input"))
      (node (ref "IC2") (pin "3") (pinfunction "+IN_3") (pintype "input"))
      (node (ref "IC2") (pin "5") (pinfunction "+IN_5") (pintype "input"))
      (node (ref "IC3") (pin "12") (pinfunction "+IN_12") (pintype "input"))
      (node (ref "IC3") (pin "3") (pinfunction "+IN_3") (pintype "input"))
      (node (ref "IC4") (pin "12") (pinfunction "+IN_12") (pintype "input"))
      (node (ref "IC4") (pin "3") (pinfunction "+IN_3") (pintype "input"))
      (node (ref "IC5") (pin "12") (pinfunction "+IN_12") (pintype "input"))
      (node (ref "IC5") (pin "3") (pinfunction "+IN_3") (pintype "input"))
      (node (ref "IC6") (pin "12") (pinfunction "+IN_12") (pintype "input"))
      (node (ref "IC6") (pin "3") (pinfunction "+IN_3") (pintype "input"))
      (node (ref "IC7") (pin "10") (pinfunction "+IN_10") (pintype "input"))
      (node (ref "IC9") (pin "13") (pinfunction "-IN_13") (pintype "input"))
      (node (ref "IC9") (pin "4") (pinfunction "-IN_4") (pintype "input"))
      (node (ref "Q13") (pin "2") (pinfunction "B_2") (pintype "passive"))
      (node (ref "Q14") (pin "2") (pinfunction "B_2") (pintype "passive"))
      (node (ref "Q15") (pin "2") (pinfunction "B_2") (pintype "passive"))
      (node (ref "Q16") (pin "2") (pinfunction "B_2") (pintype "passive"))
      (node (ref "R2") (pin "1") (pinfunction "1_1") (pintype "passive"))
      (node (ref "R20") (pin "1") (pinfunction "1_1") (pintype "passive"))
      (node (ref "R21") (pin "1") (pinfunction "1_1") (pintype "passive"))
      (node (ref "R22") (pin "1") (pinfunction "1_1") (pintype "passive"))
      (node (ref "R23") (pin "1") (pinfunction "1_1") (pintype "passive"))
      (node (ref "R28") (pin "1") (pinfunction "1_1") (pintype "passive"))
      (node (ref "R29") (pin "1") (pinfunction "1_1") (pintype "passive"))
      (node (ref "R30") (pin "1") (pinfunction "1_1") (pintype "passive"))
      (node (ref "R31") (pin "1") (pinfunction "1_1") (pintype "passive"))
      (node (ref "R37") (pin "1") (pinfunction "1_1") (pintype "passive"))
      (node (ref "R38") (pin "1") (pinfunction "1_1") (pintype "passive"))
      (node (ref "R39") (pin "1") (pinfunction "1_1") (pintype "passive"))
      (node (ref "R4") (pin "1") (pinfunction "1_1") (pintype "passive"))
      (node (ref "R40") (pin "1") (pinfunction "1_1") (pintype "passive"))
      (node (ref "R56") (pin "1") (pinfunction "1_1") (pintype "passive"))
      (node (ref "R6") (pin "1") (pinfunction "1_1") (pintype "passive"))
      (node (ref "R71") (pin "1") (pinfunction "1_1") (pintype "passive"))
      (node (ref "R74") (pin "1") (pinfunction "1_1") (pintype "passive"))
      (node (ref "R77") (pin "1") (pinfunction "1_1") (pintype "passive"))
      (node (ref "R8") (pin "1") (pinfunction "1_1") (pintype "passive"))
      (node (ref "R80") (pin "1") (pinfunction "1_1") (pintype "passive"))
      (node (ref "RV2") (pin "1") (pinfunction "A_1") (pintype "passive"))
      (node (ref "RV3") (pin "1") (pinfunction "A_1") (pintype "passive"))
      (node (ref "SV1") (pin "3") (pinfunction "3_3") (pintype "passive"))
      (node (ref "SV1") (pin "4") (pinfunction "4_4") (pintype "passive"))
      (node (ref "SV1") (pin "5") (pinfunction "5_5") (pintype "passive"))
      (node (ref "SV1") (pin "6") (pinfunction "6_6") (pintype "passive"))
      (node (ref "SV1") (pin "7") (pinfunction "7_7") (pintype "passive"))
      (node (ref "SV1") (pin "8") (pinfunction "8_8") (pintype "passive"))
      (node (ref "TP1") (pin "TP") (pinfunction "TP_TP") (pintype "input"))
      (node (ref "X1") (pin "5") (pinfunction "1_5") (pintype "passive"))
      (node (ref "X1") (pin "6") (pinfunction "1_6") (pintype "passive"))
      (node (ref "X1") (pin "7") (pinfunction "1_7") (pintype "passive"))
    )
    (net (code "9") (name "LFO_A1_CV") (class "Default")
      (node (ref "IC2") (pin "7") (pinfunction "OUT_7") (pintype "output"))
      (node (ref "R24") (pin "2") (pinfunction "2_2") (pintype "passive"))
      (node (ref "R82") (pin "2") (pinfunction "2_2") (pintype "passive"))
    )
    (net (code "10") (name "LFO_A1_OUT") (class "Default")
      (node (ref "C22") (pin "2") (pinfunction "2_2") (pintype "passive"))
      (node (ref "IC3") (pin "14") (pinfunction "OUT_14") (pintype "output"))
      (node (ref "R59") (pin "2") (pinfunction "2_2") (pintype "passive"))
      (node (ref "X1") (pin "12") (pinfunction "1_12") (pintype "passive"))
    )
    (net (code "11") (name "LFO_A1_RAW_SIN") (class "Default")
      (node (ref "IC3") (pin "10") (pinfunction "+IN_10") (pintype "input"))
      (node (ref "Q21") (pin "2") (pinfunction "S_2") (pintype "passive"))
      (node (ref "R2") (pin "2") (pinfunction "2_2") (pintype "passive"))
    )
    (net (code "12") (name "LFO_A1_SIN") (class "Default")
      (node (ref "IC11") (pin "1") (pinfunction "A_1") (pintype "tri_state"))
      (node (ref "IC3") (pin "8") (pinfunction "OUT_8") (pintype "output"))
      (node (ref "RV6") (pin "2") (pinfunction "S_2") (pintype "passive"))
    )
    (net (code "13") (name "LFO_A1_SQ") (class "Default")
      (node (ref "IC11") (pin "4") (pinfunction "A_4") (pintype "tri_state"))
      (node (ref "IC3") (pin "5") (pinfunction "+IN_5") (pintype "input"))
      (node (ref "IC9") (pin "3") (pinfunction "+IN_3") (pintype "input"))
      (node (ref "Q1") (pin "1") (pinfunction "S_1") (pintype "passive"))
      (node (ref "Q1") (pin "4") (pinfunction "S_4") (pintype "passive"))
    )
    (net (code "14") (name "LFO_A1_TRI") (class "Default")
      (node (ref "IC3") (pin "6") (pinfunction "-IN_6") (pintype "input"))
      (node (ref "IC8") (pin "1") (pinfunction "OUT_1") (pintype "output"))
      (node (ref "IC8") (pin "2") (pinfunction "-IN_2") (pintype "input"))
      (node (ref "RV5") (pin "3") (pinfunction "E_3") (pintype "passive"))
    )
    (net (code "15") (name "LFO_A2_CV") (class "Default")
      (node (ref "IC2") (pin "1") (pinfunction "OUT_1") (pintype "output"))
      (node (ref "R25") (pin "2") (pinfunction "2_2") (pintype "passive"))
      (node (ref "R87") (pin "2") (pinfunction "2_2") (pintype "passive"))
    )
    (net (code "16") (name "LFO_A2_OUT") (class "Default")
      (node (ref "C24") (pin "2") (pinfunction "2_2") (pintype "passive"))
      (node (ref "IC4") (pin "14") (pinfunction "OUT_14") (pintype "output"))
      (node (ref "R44") (pin "2") (pinfunction "2_2") (pintype "passive"))
      (node (ref "X1") (pin "10") (pinfunction "1_10") (pintype "passive"))
    )
    (net (code "17") (name "LFO_A2_RAW_SIN") (class "Default")
      (node (ref "IC4") (pin "10") (pinfunction "+IN_10") (pintype "input"))
      (node (ref "Q22") (pin "2") (pinfunction "S_2") (pintype "passive"))
      (node (ref "R4") (pin "2") (pinfunction "2_2") (pintype "passive"))
    )
    (net (code "18") (name "LFO_A2_SIN") (class "Default")
      (node (ref "IC11") (pin "11") (pinfunction "A_11") (pintype "tri_state"))
      (node (ref "IC4") (pin "8") (pinfunction "OUT_8") (pintype "output"))
      (node (ref "RV8") (pin "2") (pinfunction "S_2") (pintype "passive"))
    )
    (net (code "19") (name "LFO_A2_SQ") (class "Default")
      (node (ref "IC11") (pin "8") (pinfunction "A_8") (pintype "tri_state"))
      (node (ref "IC4") (pin "5") (pinfunction "+IN_5") (pintype "input"))
      (node (ref "IC9") (pin "14") (pinfunction "+IN_14") (pintype "input"))
      (node (ref "Q2") (pin "1") (pinfunction "S_1") (pintype "passive"))
      (node (ref "Q2") (pin "4") (pinfunction "S_4") (pintype "passive"))
    )
    (net (code "20") (name "LFO_A2_TRI") (class "Default")
      (node (ref "IC4") (pin "6") (pinfunction "-IN_6") (pintype "input"))
      (node (ref "IC8") (pin "6") (pinfunction "-IN_6") (pintype "input"))
      (node (ref "IC8") (pin "7") (pinfunction "OUT_7") (pintype "output"))
      (node (ref "RV7") (pin "3") (pinfunction "E_3") (pintype "passive"))
    )
    (net (code "21") (name "LFO_A3_CV") (class "Default")
      (node (ref "IC2") (pin "14") (pinfunction "OUT_14") (pintype "output"))
      (node (ref "R26") (pin "2") (pinfunction "2_2") (pintype "passive"))
      (node (ref "R88") (pin "2") (pinfunction "2_2") (pintype "passive"))
    )
    (net (code "22") (name "LFO_A3_OUT") (class "Default")
      (node (ref "C27") (pin "2") (pinfunction "2_2") (pintype "passive"))
      (node (ref "IC5") (pin "14") (pinfunction "OUT_14") (pintype "output"))
      (node (ref "R48") (pin "2") (pinfunction "2_2") (pintype "passive"))
      (node (ref "X1") (pin "8") (pinfunction "1_8") (pintype "passive"))
    )
    (net (code "23") (name "LFO_A3_RAW_SIN") (class "Default")
      (node (ref "IC5") (pin "10") (pinfunction "+IN_10") (pintype "input"))
      (node (ref "Q23") (pin "2") (pinfunction "S_2") (pintype "passive"))
      (node (ref "R6") (pin "2") (pinfunction "2_2") (pintype "passive"))
    )
    (net (code "24") (name "LFO_A3_SIN") (class "Default")
      (node (ref "IC12") (pin "1") (pinfunction "A_1") (pintype "tri_state"))
      (node (ref "IC5") (pin "8") (pinfunction "OUT_8") (pintype "output"))
      (node (ref "RV10") (pin "2") (pinfunction "S_2") (pintype "passive"))
    )
    (net (code "25") (name "LFO_A3_SQ") (class "Default")
      (node (ref "IC10") (pin "3") (pinfunction "+IN_3") (pintype "input"))
      (node (ref "IC12") (pin "4") (pinfunction "A_4") (pintype "tri_state"))
      (node (ref "IC5") (pin "5") (pinfunction "+IN_5") (pintype "input"))
      (node (ref "Q3") (pin "1") (pinfunction "S_1") (pintype "passive"))
      (node (ref "Q3") (pin "4") (pinfunction "S_4") (pintype "passive"))
    )
    (net (code "26") (name "LFO_A3_TRI") (class "Default")
      (node (ref "IC5") (pin "6") (pinfunction "-IN_6") (pintype "input"))
      (node (ref "IC7") (pin "1") (pinfunction "OUT_1") (pintype "output"))
      (node (ref "IC7") (pin "2") (pinfunction "-IN_2") (pintype "input"))
      (node (ref "RV9") (pin "3") (pinfunction "E_3") (pintype "passive"))
    )
    (net (code "27") (name "LFO_A4_CV") (class "Default")
      (node (ref "IC2") (pin "8") (pinfunction "OUT_8") (pintype "output"))
      (node (ref "R27") (pin "2") (pinfunction "2_2") (pintype "passive"))
      (node (ref "R90") (pin "2") (pinfunction "2_2") (pintype "passive"))
    )
    (net (code "28") (name "LFO_A4_OUT") (class "Default")
      (node (ref "C21") (pin "2") (pinfunction "2_2") (pintype "passive"))
      (node (ref "IC6") (pin "14") (pinfunction "OUT_14") (pintype "output"))
      (node (ref "R52") (pin "2") (pinfunction "2_2") (pintype "passive"))
      (node (ref "X1") (pin "1") (pinfunction "1_1") (pintype "passive"))
    )
    (net (code "29") (name "LFO_A4_RAW_SIN") (class "Default")
      (node (ref "IC6") (pin "10") (pinfunction "+IN_10") (pintype "input"))
      (node (ref "Q24") (pin "2") (pinfunction "S_2") (pintype "passive"))
      (node (ref "R8") (pin "2") (pinfunction "2_2") (pintype "passive"))
    )
    (net (code "30") (name "LFO_A4_SIN") (class "Default")
      (node (ref "IC12") (pin "11") (pinfunction "A_11") (pintype "tri_state"))
      (node (ref "IC6") (pin "8") (pinfunction "OUT_8") (pintype "output"))
      (node (ref "RV12") (pin "2") (pinfunction "S_2") (pintype "passive"))
    )
    (net (code "31") (name "LFO_A4_SQ") (class "Default")
      (node (ref "IC10") (pin "14") (pinfunction "+IN_14") (pintype "input"))
      (node (ref "IC12") (pin "8") (pinfunction "A_8") (pintype "tri_state"))
      (node (ref "IC6") (pin "5") (pinfunction "+IN_5") (pintype "input"))
      (node (ref "Q4") (pin "1") (pinfunction "S_1") (pintype "passive"))
      (node (ref "Q4") (pin "4") (pinfunction "S_4") (pintype "passive"))
    )
    (net (code "32") (name "LFO_A4_TRI") (class "Default")
      (node (ref "IC6") (pin "6") (pinfunction "-IN_6") (pintype "input"))
      (node (ref "IC7") (pin "13") (pinfunction "-IN_13") (pintype "input"))
      (node (ref "IC7") (pin "14") (pinfunction "OUT_14") (pintype "output"))
      (node (ref "RV11") (pin "3") (pinfunction "E_3") (pintype "passive"))
    )
    (net (code "33") (name "Net-(D1-PadA)") (class "Default")
      (node (ref "D1") (pin "A") (pinfunction "A_A") (pintype "passive"))
      (node (ref "SV1") (pin "10") (pinfunction "10_10") (pintype "passive"))
      (node (ref "SV1") (pin "9") (pinfunction "9_9") (pintype "passive"))
    )
    (net (code "34") (name "Net-(D2-PadC)") (class "Default")
      (node (ref "D2") (pin "C") (pinfunction "C_C") (pintype "passive"))
      (node (ref "SV1") (pin "1") (pinfunction "1_1") (pintype "passive"))
      (node (ref "SV1") (pin "2") (pinfunction "2_2") (pintype "passive"))
    )
    (net (code "35") (name "Net-(D3-A)") (class "Default")
      (node (ref "D3") (pin "3") (pinfunction "A_3") (pintype "passive"))
      (node (ref "Q22") (pin "3") (pinfunction "G_3") (pintype "passive"))
      (node (ref "R74") (pin "2") (pinfunction "2_2") (pintype "passive"))
      (node (ref "R75") (pin "1") (pinfunction "1_1") (pintype "passive"))
    )
    (net (code "36") (name "Net-(D3-C2)") (class "Default")
      (node (ref "D3") (pin "2") (pinfunction "C2_2") (pintype "passive"))
      (node (ref "R3") (pin "2") (pinfunction "2_2") (pintype "passive"))
      (node (ref "R75") (pin "2") (pinfunction "2_2") (pintype "passive"))
      (node (ref "RV7") (pin "2") (pinfunction "S_2") (pintype "passive"))
    )
    (net (code "37") (name "Net-(D4-A)") (class "Default")
      (node (ref "D4") (pin "3") (pinfunction "A_3") (pintype "passive"))
      (node (ref "Q21") (pin "3") (pinfunction "G_3") (pintype "passive"))
      (node (ref "R71") (pin "2") (pinfunction "2_2") (pintype "passive"))
      (node (ref "R72") (pin "1") (pinfunction "1_1") (pintype "passive"))
    )
    (net (code "38") (name "Net-(D4-C2)") (class "Default")
      (node (ref "D4") (pin "2") (pinfunction "C2_2") (pintype "passive"))
      (node (ref "R1") (pin "2") (pinfunction "2_2") (pintype "passive"))
      (node (ref "R72") (pin "2") (pinfunction "2_2") (pintype "passive"))
      (node (ref "RV5") (pin "2") (pinfunction "S_2") (pintype "passive"))
    )
    (net (code "39") (name "Net-(D5-A)") (class "Default")
      (node (ref "D5") (pin "3") (pinfunction "A_3") (pintype "passive"))
      (node (ref "Q23") (pin "3") (pinfunction "G_3") (pintype "passive"))
      (node (ref "R77") (pin "2") (pinfunction "2_2") (pintype "passive"))
      (node (ref "R78") (pin "1") (pinfunction "1_1") (pintype "passive"))
    )
    (net (code "40") (name "Net-(D5-C2)") (class "Default")
      (node (ref "D5") (pin "2") (pinfunction "C2_2") (pintype "passive"))
      (node (ref "R5") (pin "2") (pinfunction "2_2") (pintype "passive"))
      (node (ref "R78") (pin "2") (pinfunction "2_2") (pintype "passive"))
      (node (ref "RV9") (pin "2") (pinfunction "S_2") (pintype "passive"))
    )
    (net (code "41") (name "Net-(D6-A)") (class "Default")
      (node (ref "D6") (pin "3") (pinfunction "A_3") (pintype "passive"))
      (node (ref "Q24") (pin "3") (pinfunction "G_3") (pintype "passive"))
      (node (ref "R69") (pin "1") (pinfunction "1_1") (pintype "passive"))
      (node (ref "R80") (pin "2") (pinfunction "2_2") (pintype "passive"))
    )
    (net (code "42") (name "Net-(D6-C2)") (class "Default")
      (node (ref "D6") (pin "2") (pinfunction "C2_2") (pintype "passive"))
      (node (ref "R69") (pin "2") (pinfunction "2_2") (pintype "passive"))
      (node (ref "R7") (pin "2") (pinfunction "2_2") (pintype "passive"))
      (node (ref "RV11") (pin "2") (pinfunction "S_2") (pintype "passive"))
    )
    (net (code "43") (name "Net-(IC1A-+IN)") (class "Default")
      (node (ref "IC1") (pin "3") (pinfunction "+IN_3") (pintype "input"))
      (node (ref "R11") (pin "2") (pinfunction "2_2") (pintype "passive"))
    )
    (net (code "44") (name "Net-(IC1B-+IN)") (class "Default")
      (node (ref "IC1") (pin "5") (pinfunction "+IN_5") (pintype "input"))
      (node (ref "RV1") (pin "2") (pinfunction "S_2") (pintype "passive"))
    )
    (net (code "45") (name "Net-(IC1C-+IN)") (class "Default")
      (node (ref "IC1") (pin "10") (pinfunction "+IN_10") (pintype "input"))
      (node (ref "RV3") (pin "2") (pinfunction "S_2") (pintype "passive"))
    )
    (net (code "46") (name "Net-(IC2A--IN)") (class "Default")
      (node (ref "IC2") (pin "2") (pinfunction "-IN_2") (pintype "input"))
      (node (ref "R61") (pin "2") (pinfunction "2_2") (pintype "passive"))
      (node (ref "R66") (pin "2") (pinfunction "2_2") (pintype "passive"))
      (node (ref "R67") (pin "2") (pinfunction "2_2") (pintype "passive"))
      (node (ref "R84") (pin "2") (pinfunction "2_2") (pintype "passive"))
      (node (ref "R87") (pin "1") (pinfunction "1_1") (pintype "passive"))
      (node (ref "TP3") (pin "TP") (pinfunction "TP_TP") (pintype "input"))
    )
    (net (code "47") (name "Net-(IC2B--IN)") (class "Default")
      (node (ref "IC2") (pin "6") (pinfunction "-IN_6") (pintype "input"))
      (node (ref "R60") (pin "2") (pinfunction "2_2") (pintype "passive"))
      (node (ref "R82") (pin "1") (pinfunction "1_1") (pintype "passive"))
      (node (ref "R83") (pin "2") (pinfunction "2_2") (pintype "passive"))
      (node (ref "TP2") (pin "TP") (pinfunction "TP_TP") (pintype "input"))
    )
    (net (code "48") (name "Net-(IC2C--IN)") (class "Default")
      (node (ref "IC2") (pin "9") (pinfunction "-IN_9") (pintype "input"))
      (node (ref "R63") (pin "2") (pinfunction "2_2") (pintype "passive"))
      (node (ref "R89") (pin "2") (pinfunction "2_2") (pintype "passive"))
      (node (ref "R90") (pin "1") (pinfunction "1_1") (pintype "passive"))
      (node (ref "R91") (pin "2") (pinfunction "2_2") (pintype "passive"))
      (node (ref "R92") (pin "2") (pinfunction "2_2") (pintype "passive"))
      (node (ref "TP5") (pin "TP") (pinfunction "TP_TP") (pintype "input"))
    )
    (net (code "49") (name "Net-(IC2D--IN)") (class "Default")
      (node (ref "IC2") (pin "13") (pinfunction "-IN_13") (pintype "input"))
      (node (ref "R62") (pin "2") (pinfunction "2_2") (pintype "passive"))
      (node (ref "R64") (pin "2") (pinfunction "2_2") (pintype "passive"))
      (node (ref "R65") (pin "2") (pinfunction "2_2") (pintype "passive"))
      (node (ref "R86") (pin "2") (pinfunction "2_2") (pintype "passive"))
      (node (ref "R88") (pin "1") (pinfunction "1_1") (pintype "passive"))
      (node (ref "TP4") (pin "TP") (pinfunction "TP_TP") (pintype "input"))
    )
    (net (code "50") (name "Net-(IC3A--IN)") (class "Default")
      (node (ref "C25") (pin "1") (pinfunction "1_1") (pintype "passive"))
      (node (ref "IC3") (pin "2") (pinfunction "-IN_2") (pintype "input"))
      (node (ref "Q13") (pin "6") (pinfunction "C_6") (pintype "passive"))
      (node (ref "R70") (pin "2") (pinfunction "2_2") (pintype "passive"))
    )
    (net (code "51") (name "Net-(IC3A-OUT)") (class "Default")
      (node (ref "C25") (pin "2") (pinfunction "2_2") (pintype "passive"))
      (node (ref "IC3") (pin "1") (pinfunction "OUT_1") (pintype "output"))
      (node (ref "R16") (pin "1") (pinfunction "1_1") (pintype "passive"))
    )
    (net (code "52") (name "Net-(IC3B-OUT)") (class "Default")
      (node (ref "IC3") (pin "7") (pinfunction "OUT_7") (pintype "output"))
      (node (ref "Q1") (pin "2") (pinfunction "G_2") (pintype "passive"))
      (node (ref "Q1") (pin "5") (pinfunction "G_5") (pintype "passive"))
    )
    (net (code "53") (name "Net-(IC3C--IN)") (class "Default")
      (node (ref "IC3") (pin "9") (pinfunction "-IN_9") (pintype "input"))
      (node (ref "R28") (pin "2") (pinfunction "2_2") (pintype "passive"))
      (node (ref "RV6") (pin "1") (pinfunction "A_1") (pintype "passive"))
    )
    (net (code "54") (name "Net-(IC3D--IN)") (class "Default")
      (node (ref "C22") (pin "1") (pinfunction "1_1") (pintype "passive"))
      (node (ref "IC3") (pin "13") (pinfunction "-IN_13") (pintype "input"))
      (node (ref "R41") (pin "2") (pinfunction "2_2") (pintype "passive"))
      (node (ref "R42") (pin "2") (pinfunction "2_2") (pintype "passive"))
      (node (ref "R58") (pin "2") (pinfunction "2_2") (pintype "passive"))
      (node (ref "R59") (pin "1") (pinfunction "1_1") (pintype "passive"))
    )
    (net (code "55") (name "Net-(IC4A--IN)") (class "Default")
      (node (ref "C23") (pin "1") (pinfunction "1_1") (pintype "passive"))
      (node (ref "IC4") (pin "2") (pinfunction "-IN_2") (pintype "input"))
      (node (ref "Q14") (pin "6") (pinfunction "C_6") (pintype "passive"))
      (node (ref "R73") (pin "2") (pinfunction "2_2") (pintype "passive"))
    )
    (net (code "56") (name "Net-(IC4A-OUT)") (class "Default")
      (node (ref "C23") (pin "2") (pinfunction "2_2") (pintype "passive"))
      (node (ref "IC4") (pin "1") (pinfunction "OUT_1") (pintype "output"))
      (node (ref "R17") (pin "1") (pinfunction "1_1") (pintype "passive"))
    )
    (net (code "57") (name "Net-(IC4B-OUT)") (class "Default")
      (node (ref "IC4") (pin "7") (pinfunction "OUT_7") (pintype "output"))
      (node (ref "Q2") (pin "2") (pinfunction "G_2") (pintype "passive"))
      (node (ref "Q2") (pin "5") (pinfunction "G_5") (pintype "passive"))
    )
    (net (code "58") (name "Net-(IC4C--IN)") (class "Default")
      (node (ref "IC4") (pin "9") (pinfunction "-IN_9") (pintype "input"))
      (node (ref "R29") (pin "2") (pinfunction "2_2") (pintype "passive"))
      (node (ref "RV8") (pin "1") (pinfunction "A_1") (pintype "passive"))
    )
    (net (code "59") (name "Net-(IC4D--IN)") (class "Default")
      (node (ref "C24") (pin "1") (pinfunction "1_1") (pintype "passive"))
      (node (ref "IC4") (pin "13") (pinfunction "-IN_13") (pintype "input"))
      (node (ref "R43") (pin "2") (pinfunction "2_2") (pintype "passive"))
      (node (ref "R44") (pin "1") (pinfunction "1_1") (pintype "passive"))
      (node (ref "R45") (pin "2") (pinfunction "2_2") (pintype "passive"))
      (node (ref "R46") (pin "2") (pinfunction "2_2") (pintype "passive"))
    )
    (net (code "60") (name "Net-(IC5A--IN)") (class "Default")
      (node (ref "C26") (pin "1") (pinfunction "1_1") (pintype "passive"))
      (node (ref "IC5") (pin "2") (pinfunction "-IN_2") (pintype "input"))
      (node (ref "Q15") (pin "6") (pinfunction "C_6") (pintype "passive"))
      (node (ref "R76") (pin "2") (pinfunction "2_2") (pintype "passive"))
    )
    (net (code "61") (name "Net-(IC5A-OUT)") (class "Default")
      (node (ref "C26") (pin "2") (pinfunction "2_2") (pintype "passive"))
      (node (ref "IC5") (pin "1") (pinfunction "OUT_1") (pintype "output"))
      (node (ref "R18") (pin "1") (pinfunction "1_1") (pintype "passive"))
    )
    (net (code "62") (name "Net-(IC5B-OUT)") (class "Default")
      (node (ref "IC5") (pin "7") (pinfunction "OUT_7") (pintype "output"))
      (node (ref "Q3") (pin "2") (pinfunction "G_2") (pintype "passive"))
      (node (ref "Q3") (pin "5") (pinfunction "G_5") (pintype "passive"))
    )
    (net (code "63") (name "Net-(IC5C--IN)") (class "Default")
      (node (ref "IC5") (pin "9") (pinfunction "-IN_9") (pintype "input"))
      (node (ref "R30") (pin "2") (pinfunction "2_2") (pintype "passive"))
      (node (ref "RV10") (pin "1") (pinfunction "A_1") (pintype "passive"))
    )
    (net (code "64") (name "Net-(IC5D--IN)") (class "Default")
      (node (ref "C27") (pin "1") (pinfunction "1_1") (pintype "passive"))
      (node (ref "IC5") (pin "13") (pinfunction "-IN_13") (pintype "input"))
      (node (ref "R47") (pin "2") (pinfunction "2_2") (pintype "passive"))
      (node (ref "R48") (pin "1") (pinfunction "1_1") (pintype "passive"))
      (node (ref "R49") (pin "2") (pinfunction "2_2") (pintype "passive"))
      (node (ref "R50") (pin "2") (pinfunction "2_2") (pintype "passive"))
    )
    (net (code "65") (name "Net-(IC6A--IN)") (class "Default")
      (node (ref "C28") (pin "1") (pinfunction "1_1") (pintype "passive"))
      (node (ref "IC6") (pin "2") (pinfunction "-IN_2") (pintype "input"))
      (node (ref "Q16") (pin "6") (pinfunction "C_6") (pintype "passive"))
      (node (ref "R79") (pin "2") (pinfunction "2_2") (pintype "passive"))
    )
    (net (code "66") (name "Net-(IC6A-OUT)") (class "Default")
      (node (ref "C28") (pin "2") (pinfunction "2_2") (pintype "passive"))
      (node (ref "IC6") (pin "1") (pinfunction "OUT_1") (pintype "output"))
      (node (ref "R19") (pin "1") (pinfunction "1_1") (pintype "passive"))
    )
    (net (code "67") (name "Net-(IC6B-OUT)") (class "Default")
      (node (ref "IC6") (pin "7") (pinfunction "OUT_7") (pintype "output"))
      (node (ref "Q4") (pin "2") (pinfunction "G_2") (pintype "passive"))
      (node (ref "Q4") (pin "5") (pinfunction "G_5") (pintype "passive"))
    )
    (net (code "68") (name "Net-(IC6C--IN)") (class "Default")
      (node (ref "IC6") (pin "9") (pinfunction "-IN_9") (pintype "input"))
      (node (ref "R31") (pin "2") (pinfunction "2_2") (pintype "passive"))
      (node (ref "RV12") (pin "1") (pinfunction "A_1") (pintype "passive"))
    )
    (net (code "69") (name "Net-(IC6D--IN)") (class "Default")
      (node (ref "C21") (pin "1") (pinfunction "1_1") (pintype "passive"))
      (node (ref "IC6") (pin "13") (pinfunction "-IN_13") (pintype "input"))
      (node (ref "R51") (pin "2") (pinfunction "2_2") (pintype "passive"))
      (node (ref "R52") (pin "1") (pinfunction "1_1") (pintype "passive"))
      (node (ref "R53") (pin "2") (pinfunction "2_2") (pintype "passive"))
      (node (ref "R54") (pin "2") (pinfunction "2_2") (pintype "passive"))
    )
    (net (code "70") (name "Net-(IC7B-+IN)") (class "Default")
      (node (ref "IC7") (pin "5") (pinfunction "+IN_5") (pintype "input"))
      (node (ref "R55") (pin "1") (pinfunction "1_1") (pintype "passive"))
      (node (ref "R56") (pin "2") (pinfunction "2_2") (pintype "passive"))
    )
    (net (code "71") (name "Net-(IC7C--IN)") (class "Default")
      (node (ref "IC7") (pin "9") (pinfunction "-IN_9") (pintype "input"))
      (node (ref "R36") (pin "2") (pinfunction "2_2") (pintype "passive"))
      (node (ref "R57") (pin "1") (pinfunction "1_1") (pintype "passive"))
    )
    (net (code "72") (name "Net-(IC8A-+IN)") (class "Default")
      (node (ref "C31") (pin "1") (pinfunction "1_1") (pintype "passive"))
      (node (ref "IC8") (pin "3") (pinfunction "+IN_3") (pintype "input"))
      (node (ref "IC9") (pin "5") (pinfunction "OUT_5") (pintype "output"))
      (node (ref "Q5") (pin "2") (pinfunction "S_2") (pintype "passive"))
    )
    (net (code "73") (name "Net-(IC8B-+IN)") (class "Default")
      (node (ref "C32") (pin "1") (pinfunction "1_1") (pintype "passive"))
      (node (ref "IC8") (pin "5") (pinfunction "+IN_5") (pintype "input"))
      (node (ref "IC9") (pin "12") (pinfunction "OUT_12") (pintype "output"))
      (node (ref "Q6") (pin "2") (pinfunction "S_2") (pintype "passive"))
    )
    (net (code "74") (name "Net-(IC9A-AMP{slash}BIAS)") (class "Default")
      (node (ref "IC9") (pin "1") (pinfunction "AMP/BIAS_1") (pintype "passive"))
      (node (ref "R32") (pin "1") (pinfunction "1_1") (pintype "passive"))
    )
    (net (code "75") (name "Net-(IC9A-BUFF{slash}IN)") (class "Default")
      (node (ref "IC9") (pin "7") (pinfunction "BUFF/IN_7") (pintype "input"))
      (node (ref "IC9") (pin "8") (pinfunction "BUFF/OUT_8") (pintype "output"))
    )
    (net (code "76") (name "Net-(IC9B-AMP{slash}BIAS)") (class "Default")
      (node (ref "IC9") (pin "16") (pinfunction "AMP/BIAS_16") (pintype "passive"))
      (node (ref "R33") (pin "1") (pinfunction "1_1") (pintype "passive"))
    )
    (net (code "77") (name "Net-(IC9B-BUFF{slash}IN)") (class "Default")
      (node (ref "IC9") (pin "10") (pinfunction "BUFF/IN_10") (pintype "input"))
      (node (ref "IC9") (pin "9") (pinfunction "BUFF/OUT_9") (pintype "output"))
    )
    (net (code "78") (name "Net-(IC10A-AMP{slash}BIAS)") (class "Default")
      (node (ref "IC10") (pin "1") (pinfunction "AMP/BIAS_1") (pintype "passive"))
      (node (ref "R34") (pin "1") (pinfunction "1_1") (pintype "passive"))
    )
    (net (code "79") (name "Net-(IC10A-BUFF{slash}IN)") (class "Default")
      (node (ref "IC10") (pin "7") (pinfunction "BUFF/IN_7") (pintype "input"))
      (node (ref "IC10") (pin "8") (pinfunction "BUFF/OUT_8") (pintype "output"))
    )
    (net (code "80") (name "Net-(IC10A-OUT)") (class "Default")
      (node (ref "C29") (pin "1") (pinfunction "1_1") (pintype "passive"))
      (node (ref "IC10") (pin "5") (pinfunction "OUT_5") (pintype "output"))
      (node (ref "IC7") (pin "3") (pinfunction "+IN_3") (pintype "input"))
      (node (ref "Q7") (pin "2") (pinfunction "S_2") (pintype "passive"))
    )
    (net (code "81") (name "Net-(IC10B-AMP{slash}BIAS)") (class "Default")
      (node (ref "IC10") (pin "16") (pinfunction "AMP/BIAS_16") (pintype "passive"))
      (node (ref "R35") (pin "1") (pinfunction "1_1") (pintype "passive"))
    )
    (net (code "82") (name "Net-(IC10B-BUFF{slash}IN)") (class "Default")
      (node (ref "IC10") (pin "10") (pinfunction "BUFF/IN_10") (pintype "input"))
      (node (ref "IC10") (pin "9") (pinfunction "BUFF/OUT_9") (pintype "output"))
    )
    (net (code "83") (name "Net-(IC10B-OUT)") (class "Default")
      (node (ref "C30") (pin "1") (pinfunction "1_1") (pintype "passive"))
      (node (ref "IC10") (pin "12") (pinfunction "OUT_12") (pintype "output"))
      (node (ref "IC7") (pin "12") (pinfunction "+IN_12") (pintype "input"))
      (node (ref "Q8") (pin "2") (pinfunction "S_2") (pintype "passive"))
    )
    (net (code "84") (name "Net-(IC11A-B)") (class "Default")
      (node (ref "IC11") (pin "2") (pinfunction "B_2") (pintype "tri_state"))
      (node (ref "R58") (pin "1") (pinfunction "1_1") (pintype "passive"))
    )
    (net (code "85") (name "Net-(IC11B-B)") (class "Default")
      (node (ref "IC11") (pin "3") (pinfunction "B_3") (pintype "tri_state"))
      (node (ref "R42") (pin "1") (pinfunction "1_1") (pintype "passive"))
    )
    (net (code "86") (name "Net-(IC11C-B)") (class "Default")
      (node (ref "IC11") (pin "9") (pinfunction "B_9") (pintype "tri_state"))
      (node (ref "R46") (pin "1") (pinfunction "1_1") (pintype "passive"))
    )
    (net (code "87") (name "Net-(IC11D-B)") (class "Default")
      (node (ref "IC11") (pin "10") (pinfunction "B_10") (pintype "tri_state"))
      (node (ref "R43") (pin "1") (pinfunction "1_1") (pintype "passive"))
    )
    (net (code "88") (name "Net-(IC12A-B)") (class "Default")
      (node (ref "IC12") (pin "2") (pinfunction "B_2") (pintype "tri_state"))
      (node (ref "R47") (pin "1") (pinfunction "1_1") (pintype "passive"))
    )
    (net (code "89") (name "Net-(IC12B-B)") (class "Default")
      (node (ref "IC12") (pin "3") (pinfunction "B_3") (pintype "tri_state"))
      (node (ref "R50") (pin "1") (pinfunction "1_1") (pintype "passive"))
    )
    (net (code "90") (name "Net-(IC12C-B)") (class "Default")
      (node (ref "IC12") (pin "9") (pinfunction "B_9") (pintype "tri_state"))
      (node (ref "R54") (pin "1") (pinfunction "1_1") (pintype "passive"))
    )
    (net (code "91") (name "Net-(IC12D-B)") (class "Default")
      (node (ref "IC12") (pin "10") (pinfunction "B_10") (pintype "tri_state"))
      (node (ref "R51") (pin "1") (pinfunction "1_1") (pintype "passive"))
    )
    (net (code "92") (name "Net-(Q9-C)") (class "Default")
      (node (ref "Q9") (pin "3") (pinfunction "C_3") (pintype "passive"))
      (node (ref "R32") (pin "2") (pinfunction "2_2") (pintype "passive"))
    )
    (net (code "93") (name "Net-(Q10-B)") (class "Default")
      (node (ref "Q10") (pin "1") (pinfunction "B_1") (pintype "passive"))
      (node (ref "Q18") (pin "6") (pinfunction "C_6") (pintype "passive"))
      (node (ref "R13") (pin "2") (pinfunction "2_2") (pintype "passive"))
    )
    (net (code "94") (name "Net-(Q10-C)") (class "Default")
      (node (ref "Q10") (pin "3") (pinfunction "C_3") (pintype "passive"))
      (node (ref "R33") (pin "2") (pinfunction "2_2") (pintype "passive"))
    )
    (net (code "95") (name "Net-(Q10-E)") (class "Default")
      (node (ref "Q10") (pin "2") (pinfunction "E_2") (pintype "passive"))
      (node (ref "Q18") (pin "1") (pinfunction "B_1") (pintype "passive"))
      (node (ref "Q18") (pin "2") (pinfunction "B_2") (pintype "passive"))
      (node (ref "Q18") (pin "3") (pinfunction "C_3") (pintype "passive"))
    )
    (net (code "96") (name "Net-(Q11-B)") (class "Default")
      (node (ref "Q11") (pin "1") (pinfunction "B_1") (pintype "passive"))
      (node (ref "Q19") (pin "6") (pinfunction "C_6") (pintype "passive"))
      (node (ref "R14") (pin "2") (pinfunction "2_2") (pintype "passive"))
    )
    (net (code "97") (name "Net-(Q11-C)") (class "Default")
      (node (ref "Q11") (pin "3") (pinfunction "C_3") (pintype "passive"))
      (node (ref "R34") (pin "2") (pinfunction "2_2") (pintype "passive"))
    )
    (net (code "98") (name "Net-(Q11-E)") (class "Default")
      (node (ref "Q11") (pin "2") (pinfunction "E_2") (pintype "passive"))
      (node (ref "Q19") (pin "1") (pinfunction "B_1") (pintype "passive"))
      (node (ref "Q19") (pin "2") (pinfunction "B_2") (pintype "passive"))
      (node (ref "Q19") (pin "3") (pinfunction "C_3") (pintype "passive"))
    )
    (net (code "99") (name "Net-(Q12-B)") (class "Default")
      (node (ref "Q12") (pin "1") (pinfunction "B_1") (pintype "passive"))
      (node (ref "Q20") (pin "6") (pinfunction "C_6") (pintype "passive"))
      (node (ref "R15") (pin "2") (pinfunction "2_2") (pintype "passive"))
    )
    (net (code "100") (name "Net-(Q12-C)") (class "Default")
      (node (ref "Q12") (pin "3") (pinfunction "C_3") (pintype "passive"))
      (node (ref "R35") (pin "2") (pinfunction "2_2") (pintype "passive"))
    )
    (net (code "101") (name "Net-(Q12-E)") (class "Default")
      (node (ref "Q12") (pin "2") (pinfunction "E_2") (pintype "passive"))
      (node (ref "Q20") (pin "1") (pinfunction "B_1") (pintype "passive"))
      (node (ref "Q20") (pin "2") (pinfunction "B_2") (pintype "passive"))
      (node (ref "Q20") (pin "3") (pinfunction "C_3") (pintype "passive"))
    )
    (net (code "102") (name "Net-(Q13A-B)") (class "Default")
      (node (ref "Q13") (pin "1") (pinfunction "B_1") (pintype "passive"))
      (node (ref "R20") (pin "2") (pinfunction "2_2") (pintype "passive"))
      (node (ref "R24") (pin "1") (pinfunction "1_1") (pintype "passive"))
    )
    (net (code "103") (name "Net-(Q13A-E)") (class "Default")
      (node (ref "Q13") (pin "4") (pinfunction "E_4") (pintype "passive"))
      (node (ref "Q13") (pin "5") (pinfunction "E_5") (pintype "passive"))
      (node (ref "R16") (pin "2") (pinfunction "2_2") (pintype "passive"))
    )
    (net (code "104") (name "Net-(Q13B-C)") (class "Default")
      (node (ref "Q13") (pin "3") (pinfunction "C_3") (pintype "passive"))
      (node (ref "R12") (pin "1") (pinfunction "1_1") (pintype "passive"))
    )
    (net (code "105") (name "Net-(Q14A-B)") (class "Default")
      (node (ref "Q14") (pin "1") (pinfunction "B_1") (pintype "passive"))
      (node (ref "R21") (pin "2") (pinfunction "2_2") (pintype "passive"))
      (node (ref "R25") (pin "1") (pinfunction "1_1") (pintype "passive"))
    )
    (net (code "106") (name "Net-(Q14A-E)") (class "Default")
      (node (ref "Q14") (pin "4") (pinfunction "E_4") (pintype "passive"))
      (node (ref "Q14") (pin "5") (pinfunction "E_5") (pintype "passive"))
      (node (ref "R17") (pin "2") (pinfunction "2_2") (pintype "passive"))
    )
    (net (code "107") (name "Net-(Q14B-C)") (class "Default")
      (node (ref "Q14") (pin "3") (pinfunction "C_3") (pintype "passive"))
      (node (ref "R13") (pin "1") (pinfunction "1_1") (pintype "passive"))
    )
    (net (code "108") (name "Net-(Q15A-B)") (class "Default")
      (node (ref "Q15") (pin "1") (pinfunction "B_1") (pintype "passive"))
      (node (ref "R22") (pin "2") (pinfunction "2_2") (pintype "passive"))
      (node (ref "R26") (pin "1") (pinfunction "1_1") (pintype "passive"))
    )
    (net (code "109") (name "Net-(Q15A-E)") (class "Default")
      (node (ref "Q15") (pin "4") (pinfunction "E_4") (pintype "passive"))
      (node (ref "Q15") (pin "5") (pinfunction "E_5") (pintype "passive"))
      (node (ref "R18") (pin "2") (pinfunction "2_2") (pintype "passive"))
    )
    (net (code "110") (name "Net-(Q15B-C)") (class "Default")
      (node (ref "Q15") (pin "3") (pinfunction "C_3") (pintype "passive"))
      (node (ref "R14") (pin "1") (pinfunction "1_1") (pintype "passive"))
    )
    (net (code "111") (name "Net-(Q16A-B)") (class "Default")
      (node (ref "Q16") (pin "1") (pinfunction "B_1") (pintype "passive"))
      (node (ref "R23") (pin "2") (pinfunction "2_2") (pintype "passive"))
      (node (ref "R27") (pin "1") (pinfunction "1_1") (pintype "passive"))
    )
    (net (code "112") (name "Net-(Q16A-E)") (class "Default")
      (node (ref "Q16") (pin "4") (pinfunction "E_4") (pintype "passive"))
      (node (ref "Q16") (pin "5") (pinfunction "E_5") (pintype "passive"))
      (node (ref "R19") (pin "2") (pinfunction "2_2") (pintype "passive"))
    )
    (net (code "113") (name "Net-(Q16B-C)") (class "Default")
      (node (ref "Q16") (pin "3") (pinfunction "C_3") (pintype "passive"))
      (node (ref "R15") (pin "1") (pinfunction "1_1") (pintype "passive"))
    )
    (net (code "114") (name "Net-(Q17A-B)") (class "Default")
      (node (ref "Q17") (pin "1") (pinfunction "B_1") (pintype "passive"))
      (node (ref "Q17") (pin "2") (pinfunction "B_2") (pintype "passive"))
      (node (ref "Q17") (pin "3") (pinfunction "C_3") (pintype "passive"))
      (node (ref "Q9") (pin "2") (pinfunction "E_2") (pintype "passive"))
    )
    (net (code "115") (name "Net-(Q17A-C)") (class "Default")
      (node (ref "Q17") (pin "6") (pinfunction "C_6") (pintype "passive"))
      (node (ref "Q9") (pin "1") (pinfunction "B_1") (pintype "passive"))
      (node (ref "R12") (pin "2") (pinfunction "2_2") (pintype "passive"))
    )
    (net (code "116") (name "Net-(Q21-D)") (class "Default")
      (node (ref "Q21") (pin "1") (pinfunction "D_1") (pintype "passive"))
      (node (ref "R1") (pin "1") (pinfunction "1_1") (pintype "passive"))
    )
    (net (code "117") (name "Net-(Q22-D)") (class "Default")
      (node (ref "Q22") (pin "1") (pinfunction "D_1") (pintype "passive"))
      (node (ref "R3") (pin "1") (pinfunction "1_1") (pintype "passive"))
    )
    (net (code "118") (name "Net-(Q23-D)") (class "Default")
      (node (ref "Q23") (pin "1") (pinfunction "D_1") (pintype "passive"))
      (node (ref "R5") (pin "1") (pinfunction "1_1") (pintype "passive"))
    )
    (net (code "119") (name "Net-(Q24-D)") (class "Default")
      (node (ref "Q24") (pin "1") (pinfunction "D_1") (pintype "passive"))
      (node (ref "R7") (pin "1") (pinfunction "1_1") (pintype "passive"))
    )
    (net (code "120") (name "Net-(Q25A-S)") (class "Default")
      (node (ref "JP1") (pin "3") (pinfunction "3_3") (pintype "passive"))
      (node (ref "Q25") (pin "1") (pinfunction "S_1") (pintype "passive"))
      (node (ref "Q25") (pin "4") (pinfunction "S_4") (pintype "passive"))
    )
    (net (code "121") (name "Net-(RV2-S)") (class "Default")
      (node (ref "R11") (pin "1") (pinfunction "1_1") (pintype "passive"))
      (node (ref "RV2") (pin "2") (pinfunction "S_2") (pintype "passive"))
    )
    (net (code "122") (name "Net-(RV5-A)") (class "Default")
      (node (ref "R37") (pin "2") (pinfunction "2_2") (pintype "passive"))
      (node (ref "RV5") (pin "1") (pinfunction "A_1") (pintype "passive"))
    )
    (net (code "123") (name "Net-(RV7-A)") (class "Default")
      (node (ref "R38") (pin "2") (pinfunction "2_2") (pintype "passive"))
      (node (ref "RV7") (pin "1") (pinfunction "A_1") (pintype "passive"))
    )
    (net (code "124") (name "Net-(RV9-A)") (class "Default")
      (node (ref "R39") (pin "2") (pinfunction "2_2") (pintype "passive"))
      (node (ref "RV9") (pin "1") (pinfunction "A_1") (pintype "passive"))
    )
    (net (code "125") (name "Net-(RV11-A)") (class "Default")
      (node (ref "R40") (pin "2") (pinfunction "2_2") (pintype "passive"))
      (node (ref "RV11") (pin "1") (pinfunction "A_1") (pintype "passive"))
    )
    (net (code "126") (name "Net-(RV13-A)") (class "Default")
      (node (ref "R70") (pin "1") (pinfunction "1_1") (pintype "passive"))
      (node (ref "RV13") (pin "1") (pinfunction "A_1") (pintype "passive"))
    )
    (net (code "127") (name "Net-(RV14-A)") (class "Default")
      (node (ref "R73") (pin "1") (pinfunction "1_1") (pintype "passive"))
      (node (ref "RV14") (pin "1") (pinfunction "A_1") (pintype "passive"))
    )
    (net (code "128") (name "Net-(RV15-A)") (class "Default")
      (node (ref "R76") (pin "1") (pinfunction "1_1") (pintype "passive"))
      (node (ref "RV15") (pin "1") (pinfunction "A_1") (pintype "passive"))
    )
    (net (code "129") (name "Net-(RV16-A)") (class "Default")
      (node (ref "R79") (pin "1") (pinfunction "1_1") (pintype "passive"))
      (node (ref "RV16") (pin "1") (pinfunction "A_1") (pintype "passive"))
    )
    (net (code "130") (name "OUTPUT_OFFSET") (class "Default")
      (node (ref "R41") (pin "1") (pinfunction "1_1") (pintype "passive"))
      (node (ref "R45") (pin "1") (pinfunction "1_1") (pintype "passive"))
      (node (ref "R49") (pin "1") (pinfunction "1_1") (pintype "passive"))
      (node (ref "R53") (pin "1") (pinfunction "1_1") (pintype "passive"))
      (node (ref "SW1") (pin "2") (pinfunction "PR_2") (pintype "passive"))
    )
    (net (code "131") (name "RESET_G") (class "Default")
      (node (ref "Q25") (pin "2") (pinfunction "G_2") (pintype "passive"))
      (node (ref "Q25") (pin "5") (pinfunction "G_5") (pintype "passive"))
      (node (ref "Q5") (pin "1") (pinfunction "G_1") (pintype "passive"))
      (node (ref "Q6") (pin "1") (pinfunction "G_1") (pintype "passive"))
      (node (ref "Q7") (pin "1") (pinfunction "G_1") (pintype "passive"))
      (node (ref "Q8") (pin "1") (pinfunction "G_1") (pintype "passive"))
      (node (ref "X1") (pin "9") (pinfunction "1_9") (pintype "passive"))
    )
    (net (code "132") (name "SINE_SW") (class "Default")
      (node (ref "IC11") (pin "12") (pinfunction "C_12") (pintype "input"))
      (node (ref "IC11") (pin "13") (pinfunction "C_13") (pintype "input"))
      (node (ref "IC12") (pin "12") (pinfunction "C_12") (pintype "input"))
      (node (ref "IC12") (pin "13") (pinfunction "C_13") (pintype "input"))
      (node (ref "R85") (pin "2") (pinfunction "2_2") (pintype "passive"))
      (node (ref "SW2") (pin "3") (pinfunction "RD_3") (pintype "passive"))
    )
    (net (code "133") (name "SPEED_A_CV") (class "Default")
      (node (ref "IC1") (pin "1") (pinfunction "OUT_1") (pintype "output"))
      (node (ref "IC1") (pin "2") (pinfunction "-IN_2") (pintype "input"))
      (node (ref "R83") (pin "1") (pinfunction "1_1") (pintype "passive"))
      (node (ref "R84") (pin "1") (pinfunction "1_1") (pintype "passive"))
      (node (ref "R86") (pin "1") (pinfunction "1_1") (pintype "passive"))
      (node (ref "R92") (pin "1") (pinfunction "1_1") (pintype "passive"))
    )
    (net (code "134") (name "SPEED_A_CV_IN") (class "Default")
      (node (ref "RV2") (pin "3") (pinfunction "E_3") (pintype "passive"))
      (node (ref "X1") (pin "13") (pinfunction "1_13") (pintype "passive"))
    )
    (net (code "135") (name "SPEED_A_POT") (class "Default")
      (node (ref "IC1") (pin "6") (pinfunction "-IN_6") (pintype "input"))
      (node (ref "IC1") (pin "7") (pinfunction "OUT_7") (pintype "output"))
      (node (ref "R60") (pin "1") (pinfunction "1_1") (pintype "passive"))
      (node (ref "R61") (pin "1") (pinfunction "1_1") (pintype "passive"))
      (node (ref "R62") (pin "1") (pinfunction "1_1") (pintype "passive"))
      (node (ref "R63") (pin "1") (pinfunction "1_1") (pintype "passive"))
    )
    (net (code "136") (name "SPEED_B_CV") (class "Default")
      (node (ref "RV4") (pin "2") (pinfunction "S_2") (pintype "passive"))
      (node (ref "X1") (pin "3") (pinfunction "1_3") (pintype "passive"))
    )
    (net (code "137") (name "SPREAD_CV") (class "Default")
      (node (ref "IC1") (pin "13") (pinfunction "-IN_13") (pintype "input"))
      (node (ref "IC1") (pin "14") (pinfunction "OUT_14") (pintype "output"))
      (node (ref "R65") (pin "1") (pinfunction "1_1") (pintype "passive"))
      (node (ref "R67") (pin "1") (pinfunction "1_1") (pintype "passive"))
      (node (ref "R91") (pin "1") (pinfunction "1_1") (pintype "passive"))
    )
    (net (code "138") (name "SPREAD_CV_IN") (class "Default")
      (node (ref "IC1") (pin "12") (pinfunction "+IN_12") (pintype "input"))
      (node (ref "X1") (pin "11") (pinfunction "1_11") (pintype "passive"))
    )
    (net (code "139") (name "SPREAD_POT") (class "Default")
      (node (ref "IC1") (pin "8") (pinfunction "OUT_8") (pintype "output"))
      (node (ref "IC1") (pin "9") (pinfunction "-IN_9") (pintype "input"))
      (node (ref "R64") (pin "1") (pinfunction "1_1") (pintype "passive"))
      (node (ref "R66") (pin "1") (pinfunction "1_1") (pintype "passive"))
      (node (ref "R89") (pin "1") (pinfunction "1_1") (pintype "passive"))
    )
    (net (code "140") (name "SQ_-5V") (class "Default")
      (node (ref "JP1") (pin "2") (pinfunction "2_2") (pintype "passive"))
      (node (ref "Q1") (pin "3") (pinfunction "D_3") (pintype "passive"))
      (node (ref "Q2") (pin "3") (pinfunction "D_3") (pintype "passive"))
      (node (ref "Q3") (pin "3") (pinfunction "D_3") (pintype "passive"))
      (node (ref "Q4") (pin "3") (pinfunction "D_3") (pintype "passive"))
    )
    (net (code "141") (name "SQ_SW") (class "Default")
      (node (ref "IC11") (pin "5") (pinfunction "C_5") (pintype "input"))
      (node (ref "IC11") (pin "6") (pinfunction "C_6") (pintype "input"))
      (node (ref "IC12") (pin "5") (pinfunction "C_5") (pintype "input"))
      (node (ref "IC12") (pin "6") (pinfunction "C_6") (pintype "input"))
      (node (ref "R81") (pin "2") (pinfunction "2_2") (pintype "passive"))
      (node (ref "SW2") (pin "1") (pinfunction "RU_1") (pintype "passive"))
    )
    (net (code "142") (name "unconnected-(IC9A-DIODE{slash}BIAS-Pad2)") (class "Default")
      (node (ref "IC9") (pin "2") (pinfunction "DIODE/BIAS_2") (pintype "passive"))
    )
    (net (code "143") (name "unconnected-(IC9B-DIODE{slash}BIAS-Pad15)") (class "Default")
      (node (ref "IC9") (pin "15") (pinfunction "DIODE/BIAS_15") (pintype "passive"))
    )
    (net (code "144") (name "unconnected-(IC10A-DIODE{slash}BIAS-Pad2)") (class "Default")
      (node (ref "IC10") (pin "2") (pinfunction "DIODE/BIAS_2") (pintype "passive"))
    )
    (net (code "145") (name "unconnected-(IC10B-DIODE{slash}BIAS-Pad15)") (class "Default")
      (node (ref "IC10") (pin "15") (pinfunction "DIODE/BIAS_15") (pintype "passive"))
    )
    (net (code "146") (name "unconnected-(RV6-E-Pad3)") (class "Default")
      (node (ref "RV6") (pin "3") (pinfunction "E_3") (pintype "passive"))
    )
    (net (code "147") (name "unconnected-(RV8-E-Pad3)") (class "Default")
      (node (ref "RV8") (pin "3") (pinfunction "E_3") (pintype "passive"))
    )
    (net (code "148") (name "unconnected-(RV10-E-Pad3)") (class "Default")
      (node (ref "RV10") (pin "3") (pinfunction "E_3") (pintype "passive"))
    )
    (net (code "149") (name "unconnected-(RV12-E-Pad3)") (class "Default")
      (node (ref "RV12") (pin "3") (pinfunction "E_3") (pintype "passive"))
    )
    (net (code "150") (name "unconnected-(RV13-E-Pad3)") (class "Default")
      (node (ref "RV13") (pin "3") (pinfunction "E_3") (pintype "passive"))
    )
    (net (code "151") (name "unconnected-(RV14-E-Pad3)") (class "Default")
      (node (ref "RV14") (pin "3") (pinfunction "E_3") (pintype "passive"))
    )
    (net (code "152") (name "unconnected-(RV15-E-Pad3)") (class "Default")
      (node (ref "RV15") (pin "3") (pinfunction "E_3") (pintype "passive"))
    )
    (net (code "153") (name "unconnected-(RV16-E-Pad3)") (class "Default")
      (node (ref "RV16") (pin "3") (pinfunction "E_3") (pintype "passive"))
    )
    (net (code "154") (name "unconnected-(SV1-Pad11)") (class "Default")
      (node (ref "SV1") (pin "11") (pinfunction "11_11") (pintype "passive"))
    )
    (net (code "155") (name "unconnected-(SV1-Pad12)") (class "Default")
      (node (ref "SV1") (pin "12") (pinfunction "12_12") (pintype "passive"))
    )
    (net (code "156") (name "unconnected-(SV1-Pad13)") (class "Default")
      (node (ref "SV1") (pin "13") (pinfunction "13_13") (pintype "passive"))
    )
    (net (code "157") (name "unconnected-(SV1-Pad14)") (class "Default")
      (node (ref "SV1") (pin "14") (pinfunction "14_14") (pintype "passive"))
    )
    (net (code "158") (name "unconnected-(SV1-Pad15)") (class "Default")
      (node (ref "SV1") (pin "15") (pinfunction "15_15") (pintype "passive"))
    )
    (net (code "159") (name "unconnected-(SV1-Pad16)") (class "Default")
      (node (ref "SV1") (pin "16") (pinfunction "16_16") (pintype "passive"))
    )
  )
)
